# Matrix.net
KiCad netlist of a schematic drawn in EAGLE
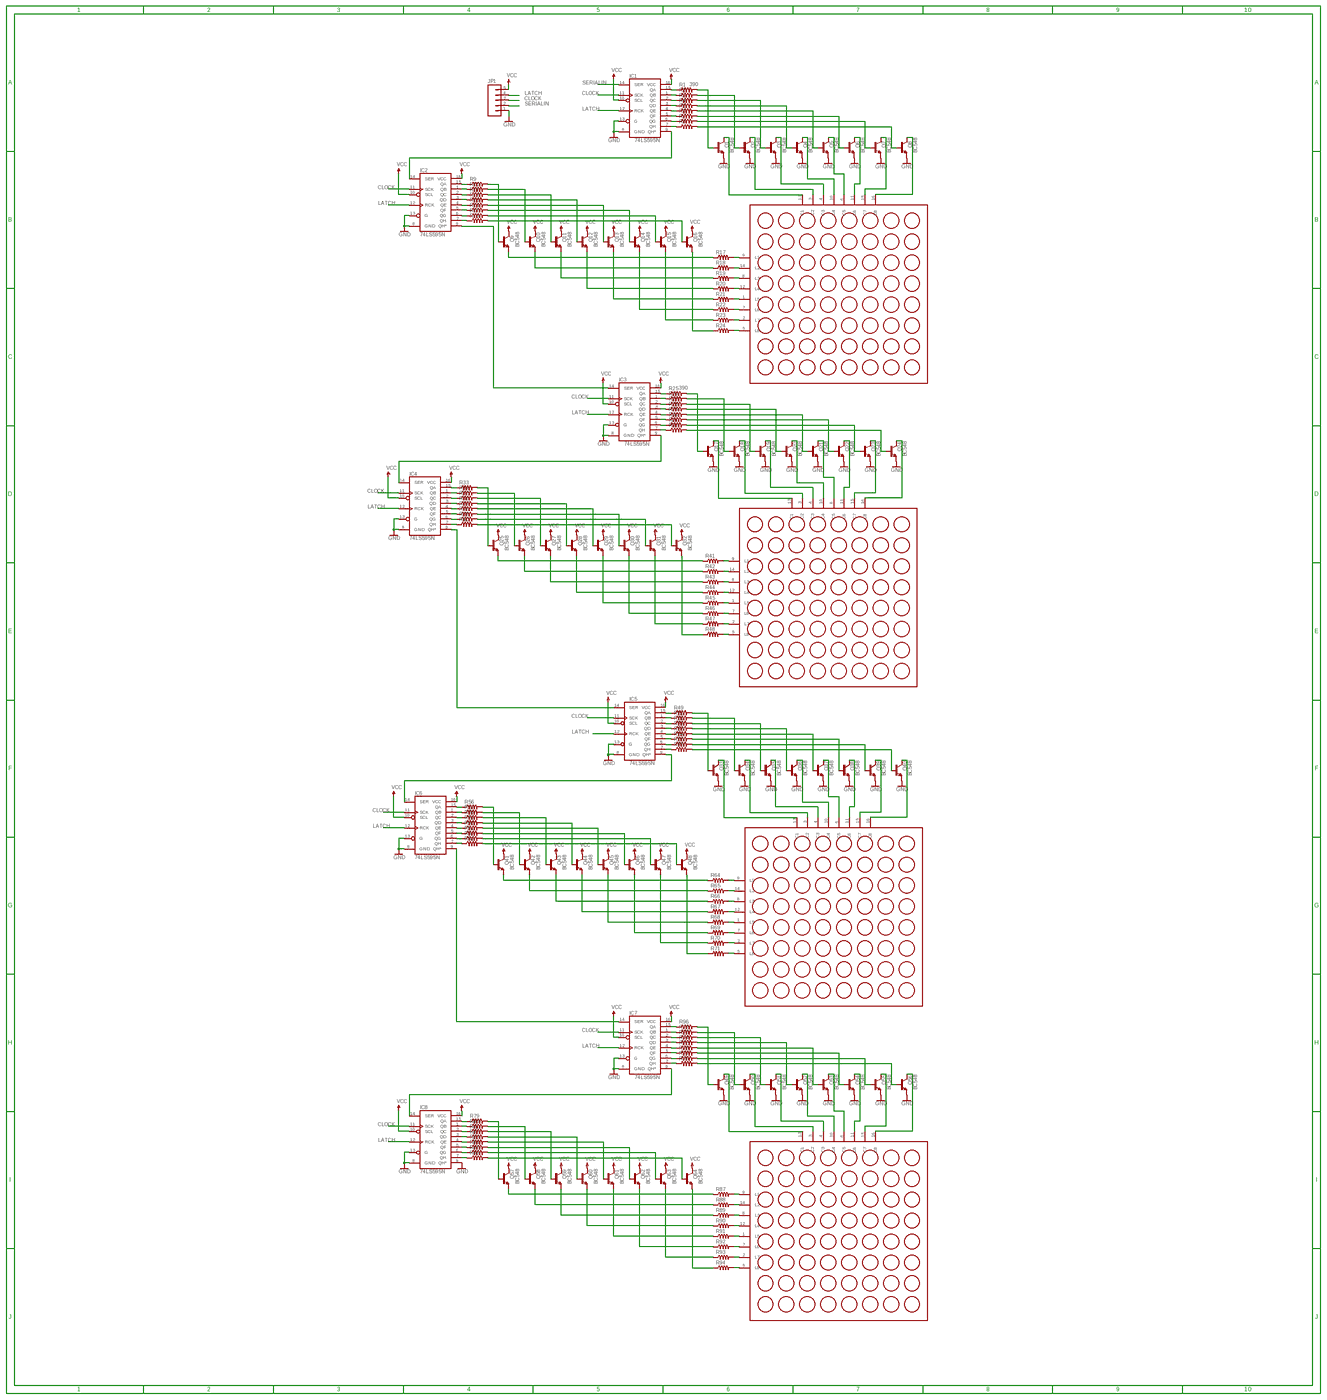
[diagram p0: schematic, sheet 1, overview]
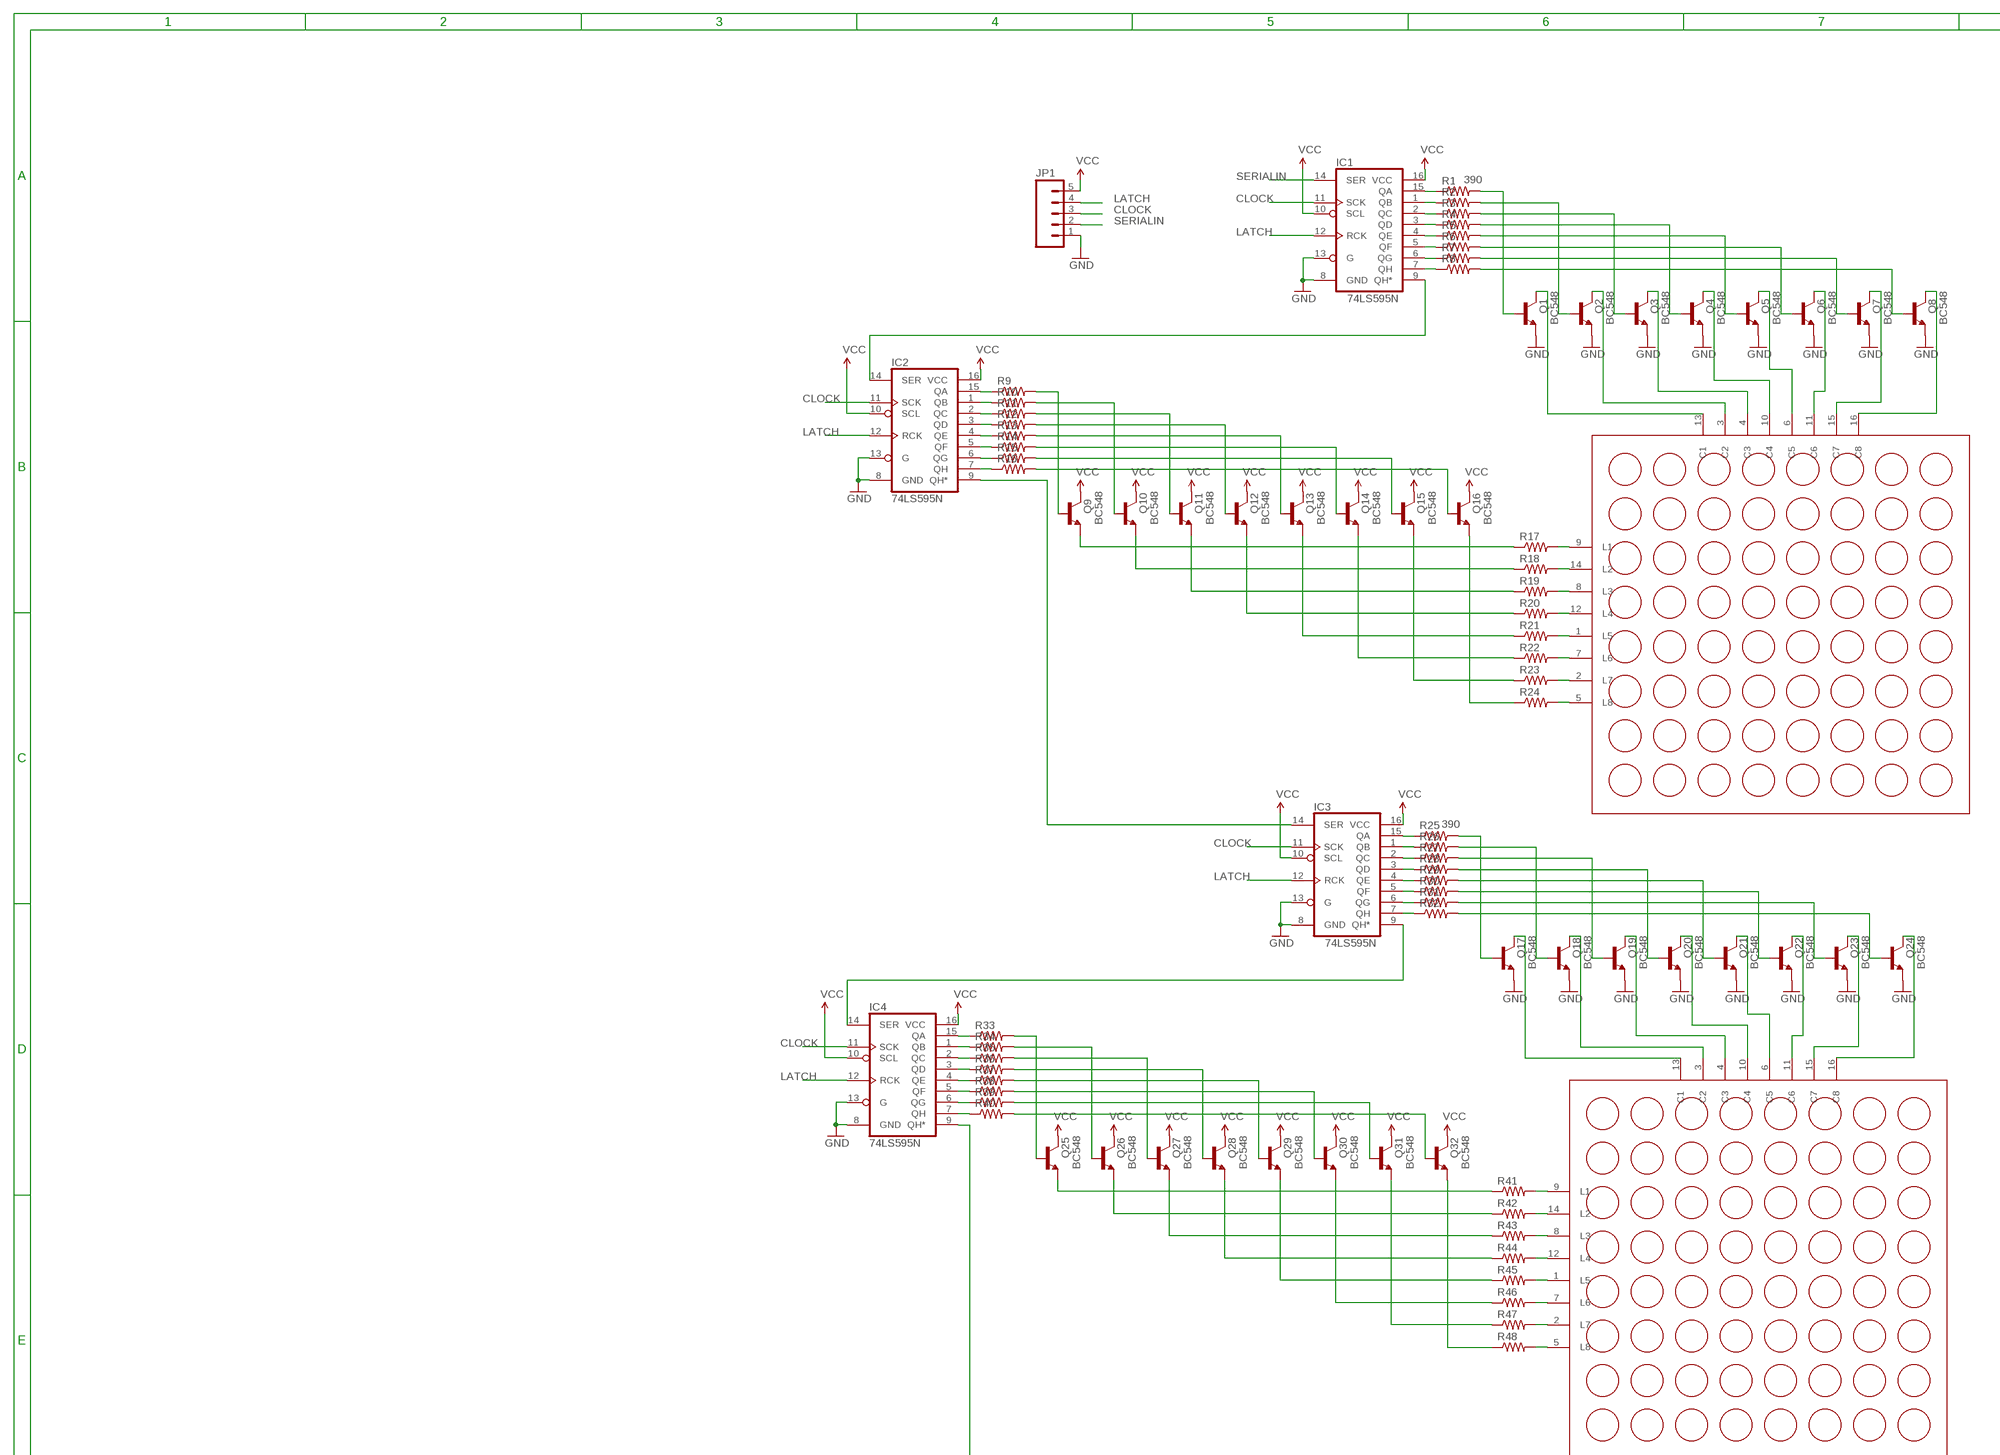
[diagram p1: schematic, sheet 1, part 1 of 4]
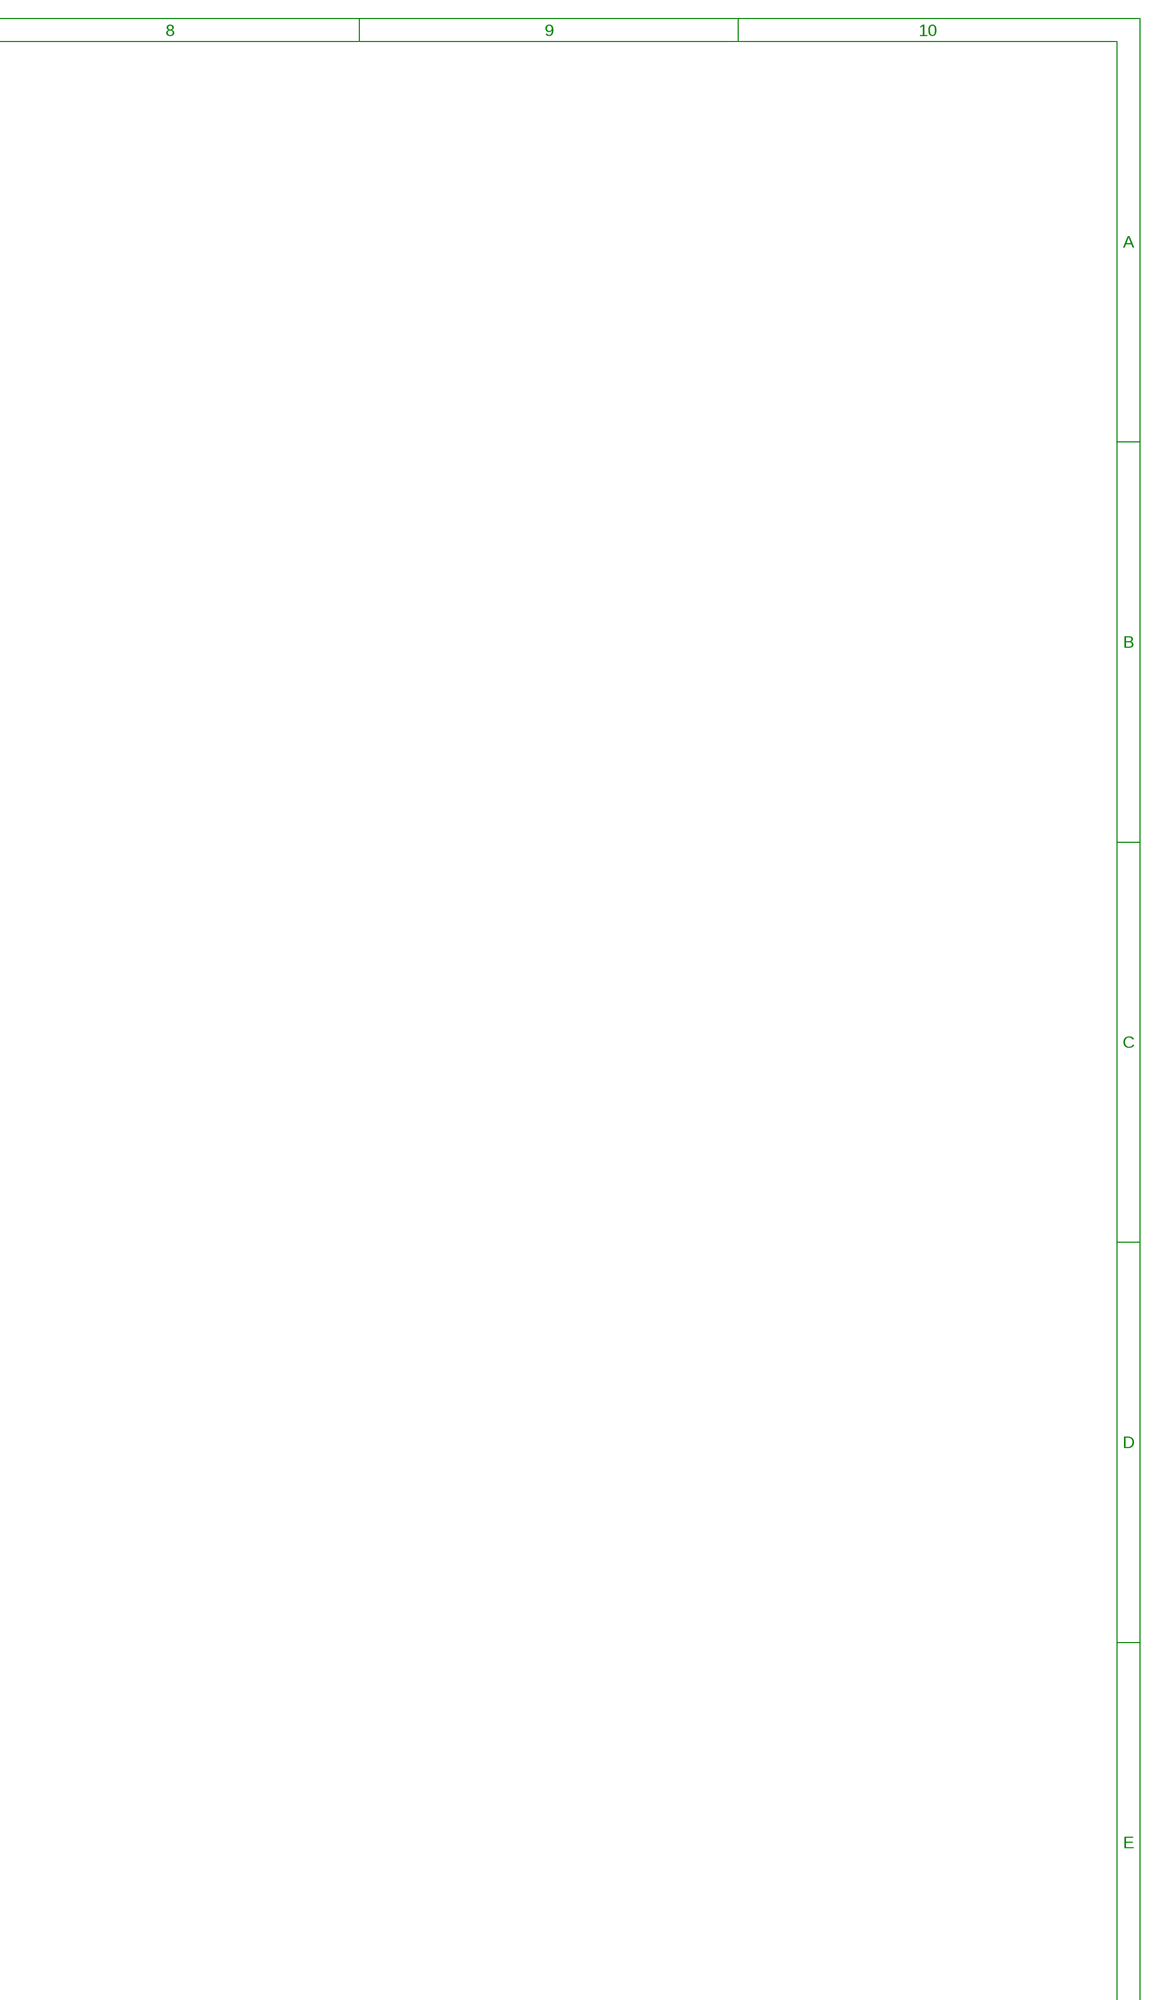
[diagram p2: schematic, sheet 1, part 2 of 4]
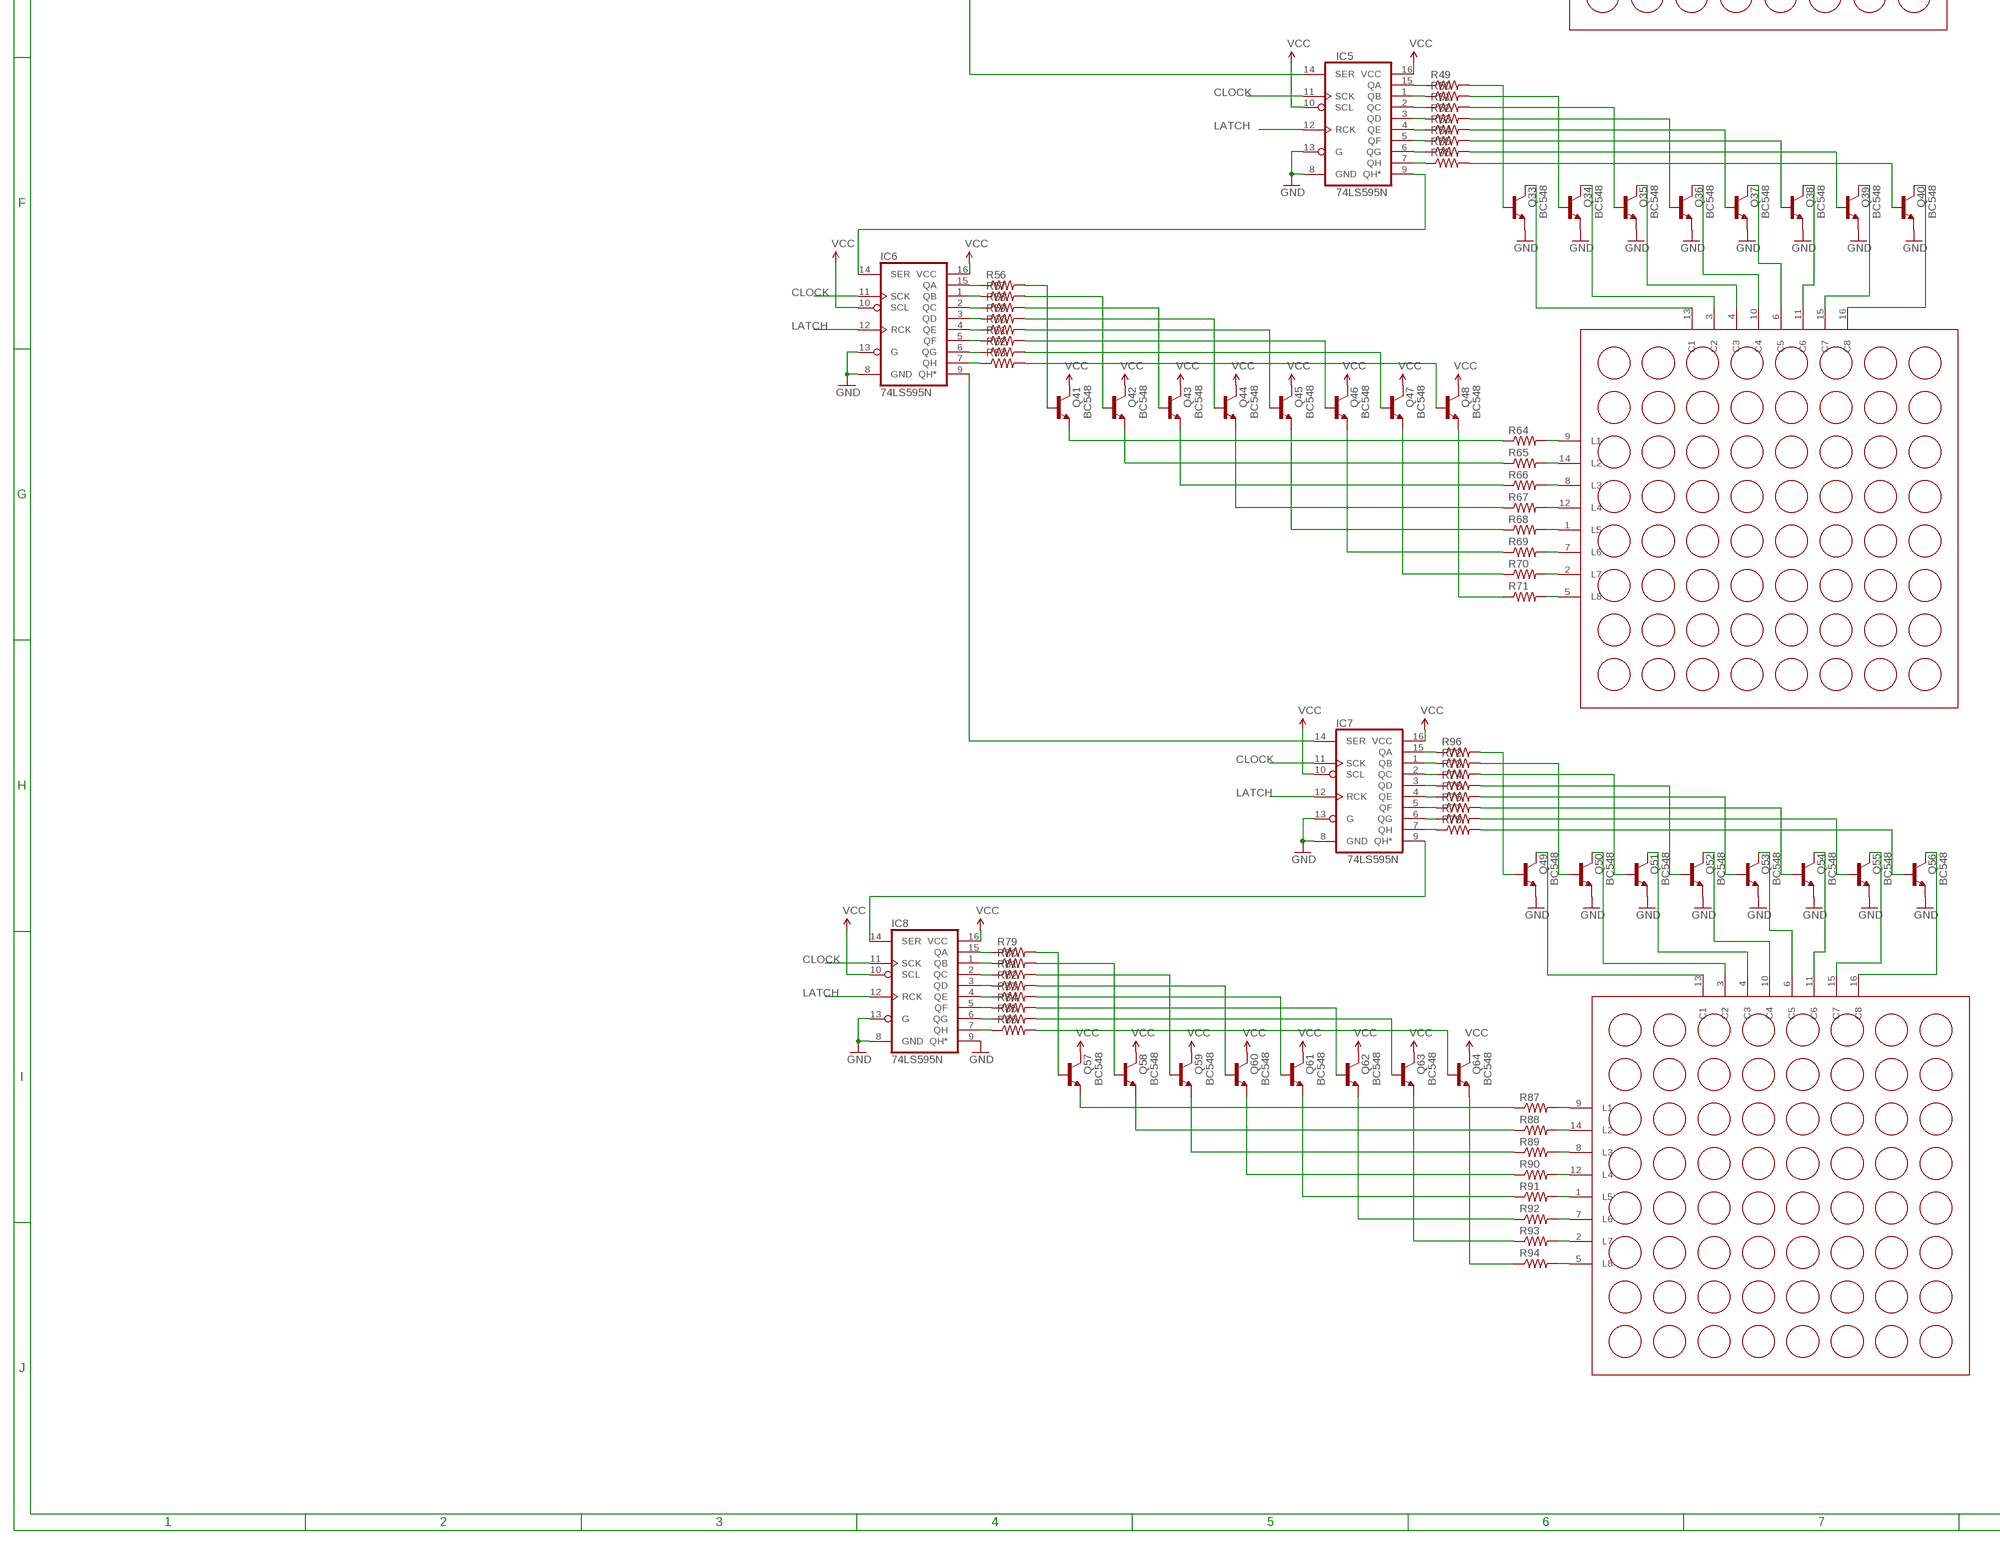
[diagram p3: schematic, sheet 1, part 3 of 4]
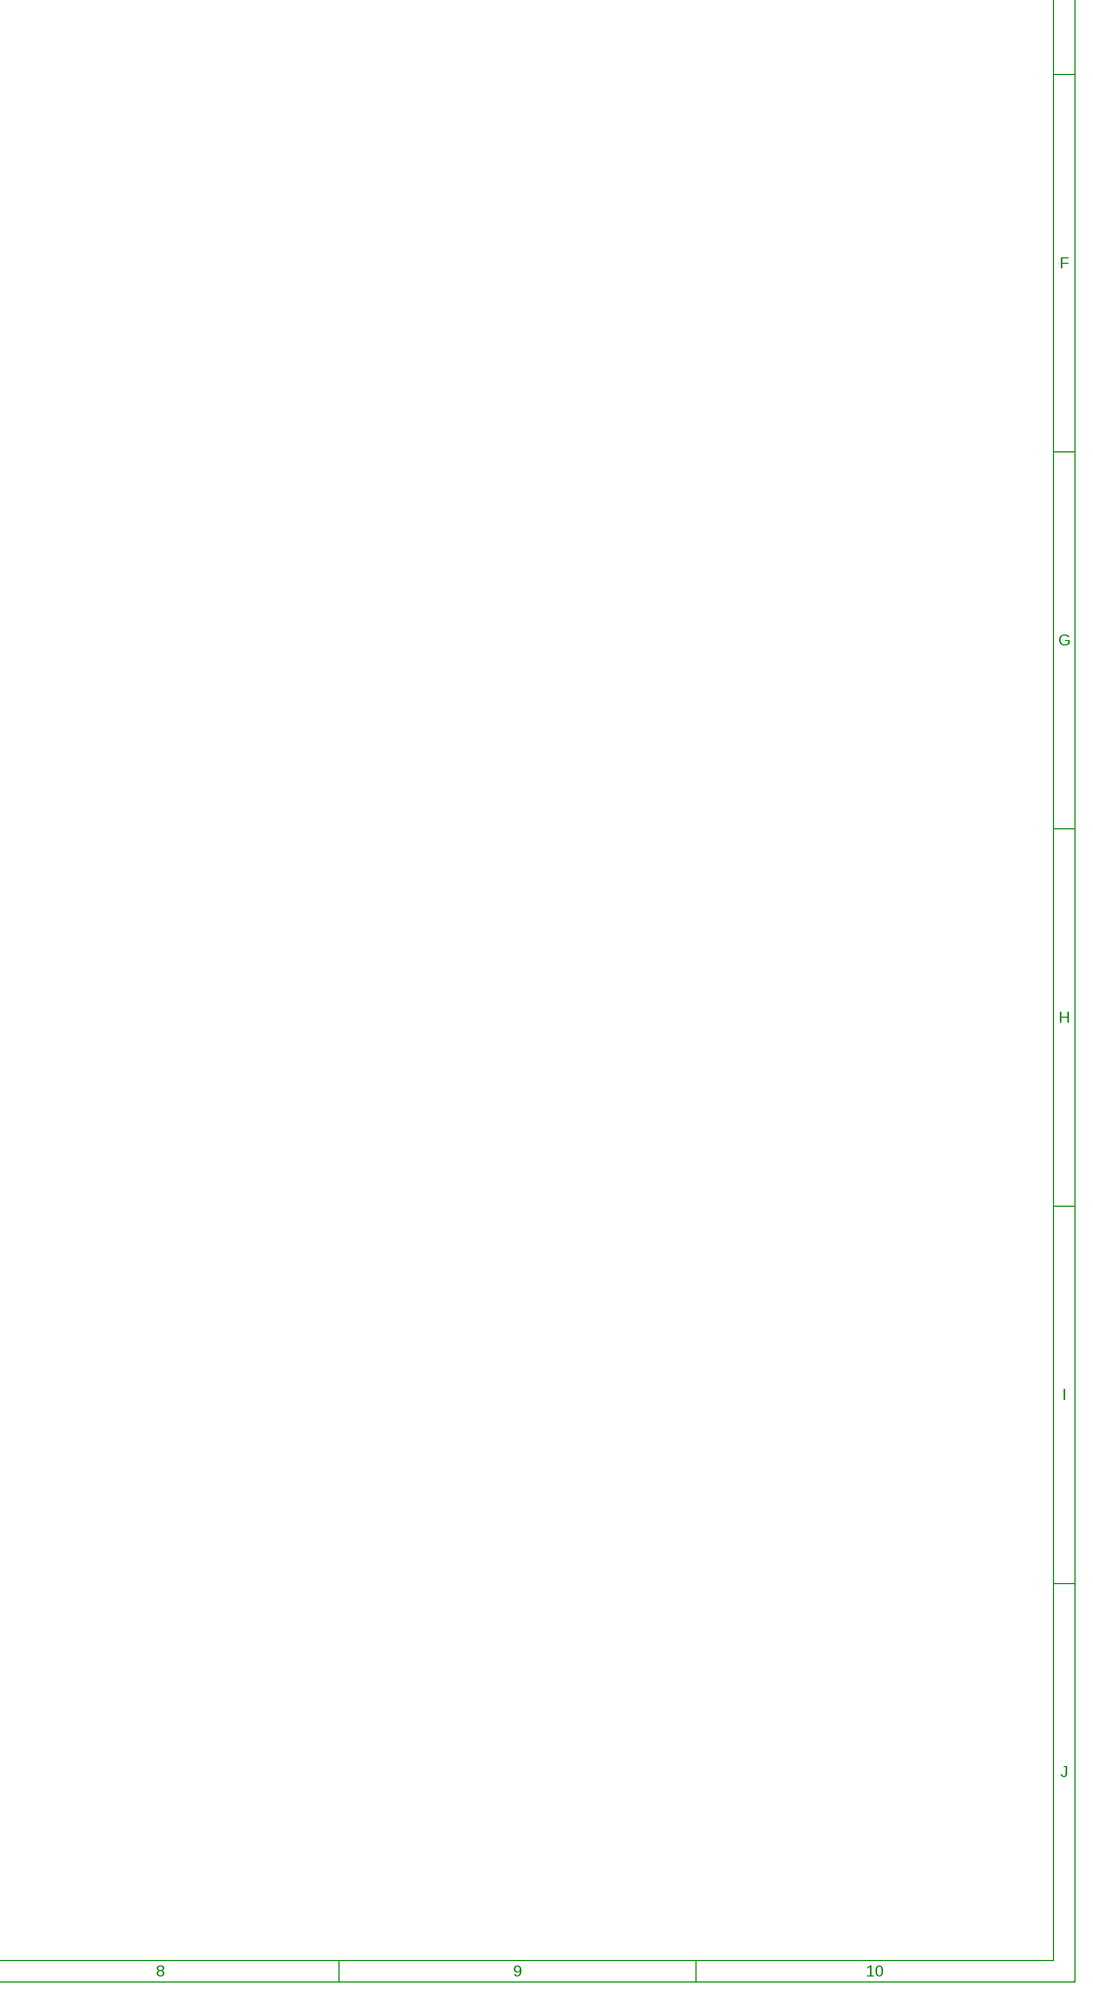
[diagram p4: schematic, sheet 1, part 4 of 4]
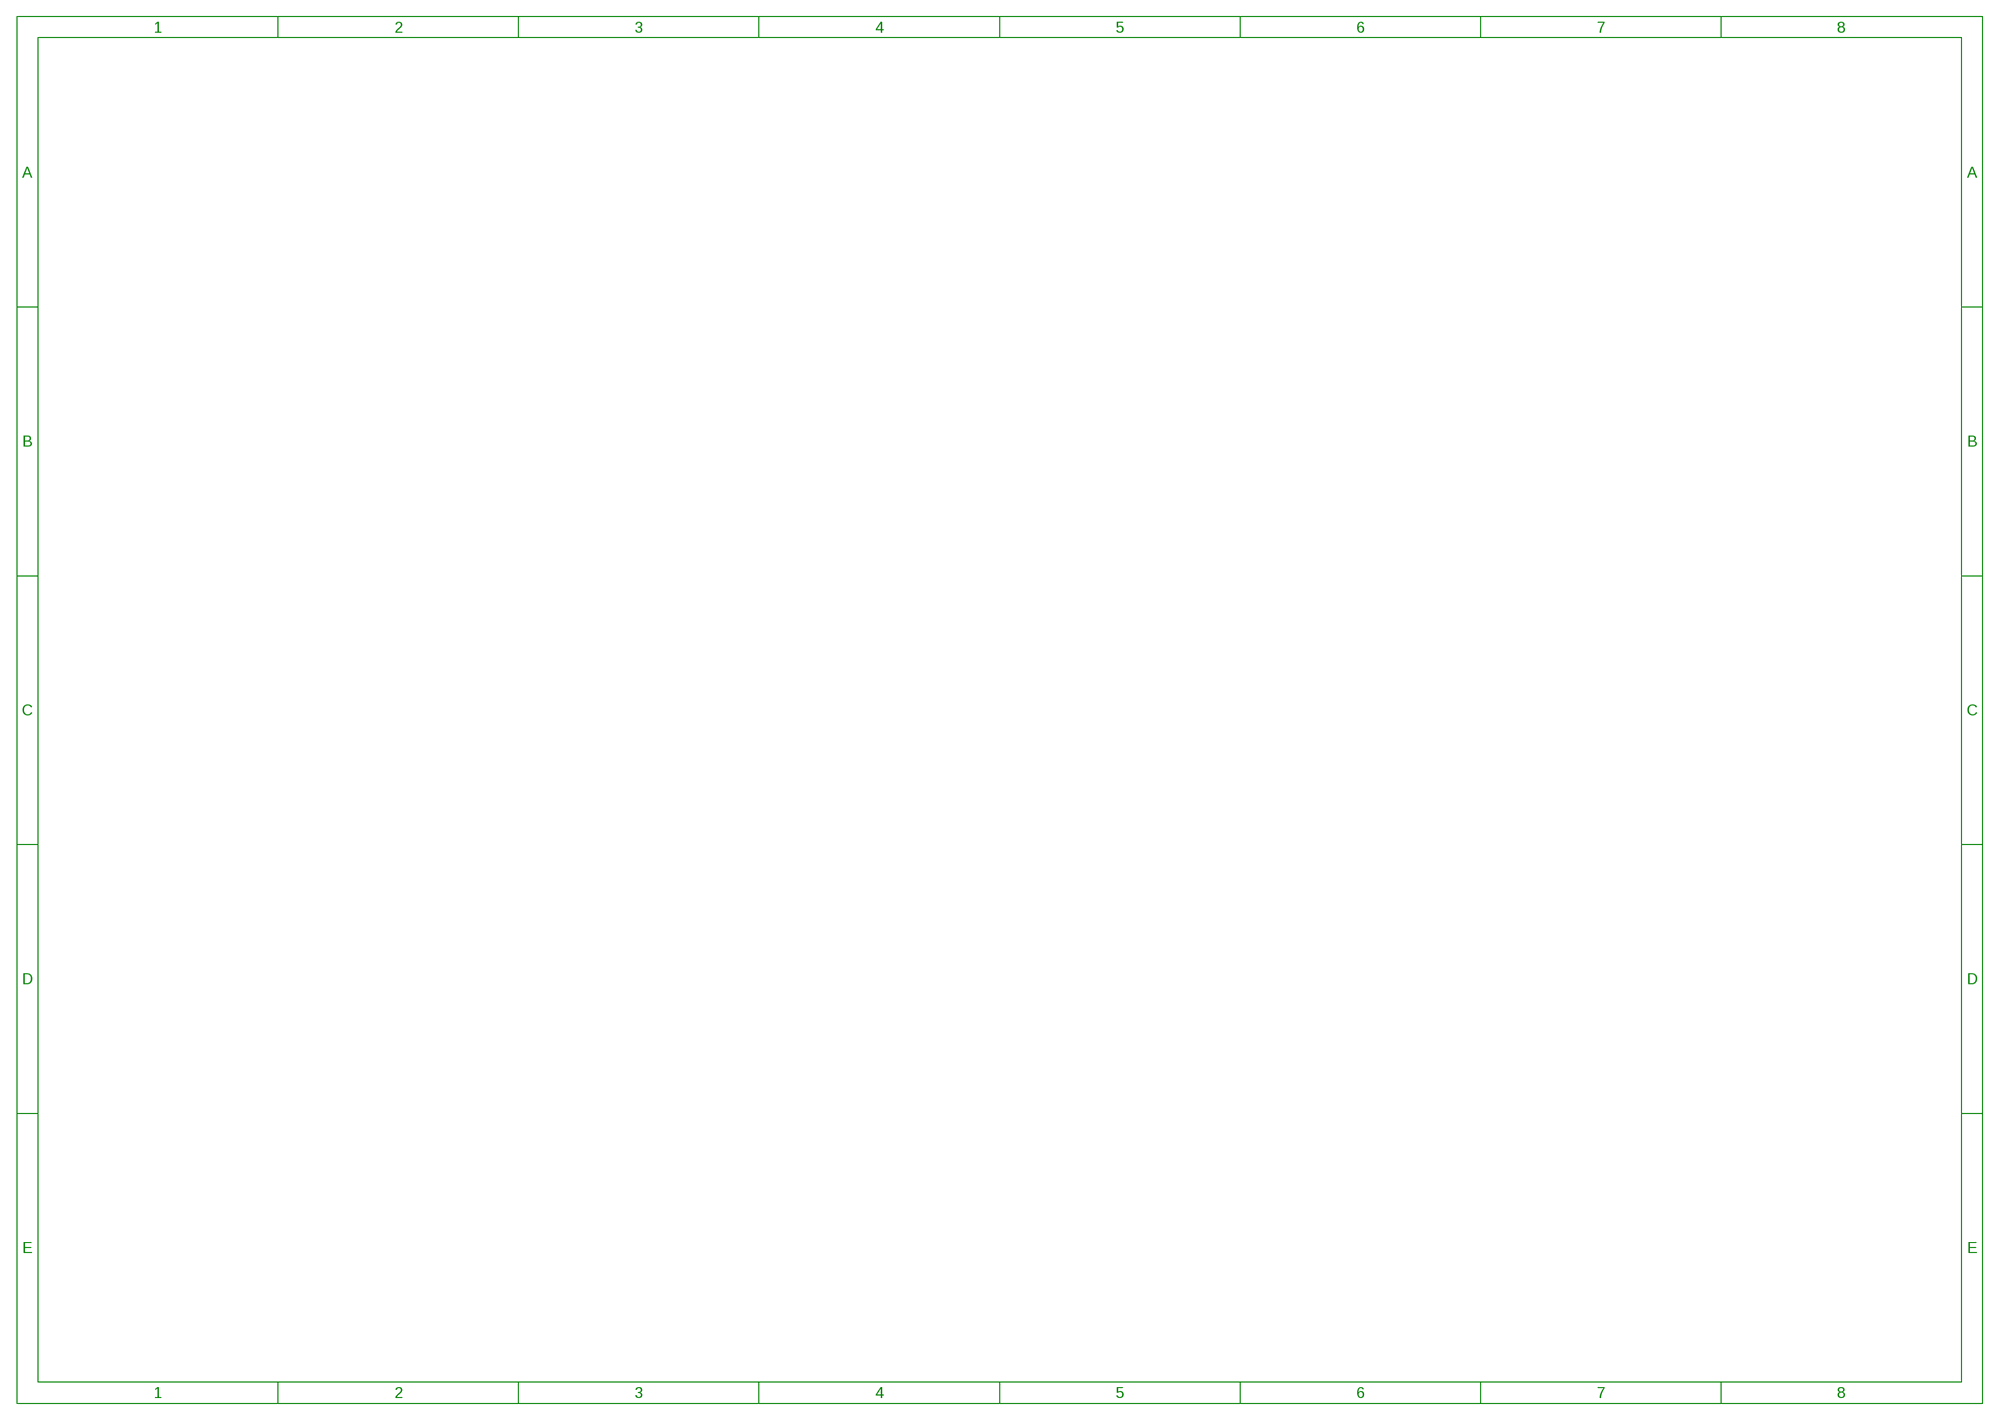
[diagram p5: schematic, sheet 2]

(export (version "E")
  (design (tool "Eeschema 10.0.6"))
  (components
    (comp (ref "IC1")
      (value "74LS595N")
      (footprint "eagle-import:DIL16")
      (libsource (lib "eagle-import") (part "74595NLS"))
    )
    (comp (ref "IC2")
      (value "74LS595N")
      (footprint "eagle-import:DIL16")
      (libsource (lib "eagle-import") (part "74595NLS"))
    )
    (comp (ref "IC3")
      (value "74LS595N")
      (footprint "eagle-import:DIL16")
      (libsource (lib "eagle-import") (part "74595NLS"))
    )
    (comp (ref "IC4")
      (value "74LS595N")
      (footprint "eagle-import:DIL16")
      (libsource (lib "eagle-import") (part "74595NLS"))
    )
    (comp (ref "IC5")
      (value "74LS595N")
      (footprint "eagle-import:DIL16")
      (libsource (lib "eagle-import") (part "74595NLS"))
    )
    (comp (ref "IC6")
      (value "74LS595N")
      (footprint "eagle-import:DIL16")
      (libsource (lib "eagle-import") (part "74595NLS"))
    )
    (comp (ref "IC7")
      (value "74LS595N")
      (footprint "eagle-import:DIL16")
      (libsource (lib "eagle-import") (part "74595NLS"))
    )
    (comp (ref "IC8")
      (value "74LS595N")
      (footprint "eagle-import:DIL16")
      (libsource (lib "eagle-import") (part "74595NLS"))
    )
    (comp (ref "JP1")
      (value "M05PTH_LONGPADS")
      (footprint "eagle-import:1X05_LONGPADS")
      (libsource (lib "eagle-import") (part "M05PTH_LONGPADS"))
    )
    (comp (ref "Q1")
      (value "BC548")
      (footprint "eagle-import:TO92-EBC")
      (libsource (lib "eagle-import") (part "BC548"))
    )
    (comp (ref "Q2")
      (value "BC548")
      (footprint "eagle-import:TO92-EBC")
      (libsource (lib "eagle-import") (part "BC548"))
    )
    (comp (ref "Q3")
      (value "BC548")
      (footprint "eagle-import:TO92-EBC")
      (libsource (lib "eagle-import") (part "BC548"))
    )
    (comp (ref "Q4")
      (value "BC548")
      (footprint "eagle-import:TO92-EBC")
      (libsource (lib "eagle-import") (part "BC548"))
    )
    (comp (ref "Q5")
      (value "BC548")
      (footprint "eagle-import:TO92-EBC")
      (libsource (lib "eagle-import") (part "BC548"))
    )
    (comp (ref "Q6")
      (value "BC548")
      (footprint "eagle-import:TO92-EBC")
      (libsource (lib "eagle-import") (part "BC548"))
    )
    (comp (ref "Q7")
      (value "BC548")
      (footprint "eagle-import:TO92-EBC")
      (libsource (lib "eagle-import") (part "BC548"))
    )
    (comp (ref "Q8")
      (value "BC548")
      (footprint "eagle-import:TO92-EBC")
      (libsource (lib "eagle-import") (part "BC548"))
    )
    (comp (ref "Q9")
      (value "BC548")
      (footprint "eagle-import:TO92-EBC")
      (libsource (lib "eagle-import") (part "BC548"))
    )
    (comp (ref "Q10")
      (value "BC548")
      (footprint "eagle-import:TO92-EBC")
      (libsource (lib "eagle-import") (part "BC548"))
    )
    (comp (ref "Q11")
      (value "BC548")
      (footprint "eagle-import:TO92-EBC")
      (libsource (lib "eagle-import") (part "BC548"))
    )
    (comp (ref "Q12")
      (value "BC548")
      (footprint "eagle-import:TO92-EBC")
      (libsource (lib "eagle-import") (part "BC548"))
    )
    (comp (ref "Q13")
      (value "BC548")
      (footprint "eagle-import:TO92-EBC")
      (libsource (lib "eagle-import") (part "BC548"))
    )
    (comp (ref "Q14")
      (value "BC548")
      (footprint "eagle-import:TO92-EBC")
      (libsource (lib "eagle-import") (part "BC548"))
    )
    (comp (ref "Q15")
      (value "BC548")
      (footprint "eagle-import:TO92-EBC")
      (libsource (lib "eagle-import") (part "BC548"))
    )
    (comp (ref "Q16")
      (value "BC548")
      (footprint "eagle-import:TO92-EBC")
      (libsource (lib "eagle-import") (part "BC548"))
    )
    (comp (ref "Q17")
      (value "BC548")
      (footprint "eagle-import:TO92-EBC")
      (libsource (lib "eagle-import") (part "BC548"))
    )
    (comp (ref "Q18")
      (value "BC548")
      (footprint "eagle-import:TO92-EBC")
      (libsource (lib "eagle-import") (part "BC548"))
    )
    (comp (ref "Q19")
      (value "BC548")
      (footprint "eagle-import:TO92-EBC")
      (libsource (lib "eagle-import") (part "BC548"))
    )
    (comp (ref "Q20")
      (value "BC548")
      (footprint "eagle-import:TO92-EBC")
      (libsource (lib "eagle-import") (part "BC548"))
    )
    (comp (ref "Q21")
      (value "BC548")
      (footprint "eagle-import:TO92-EBC")
      (libsource (lib "eagle-import") (part "BC548"))
    )
    (comp (ref "Q22")
      (value "BC548")
      (footprint "eagle-import:TO92-EBC")
      (libsource (lib "eagle-import") (part "BC548"))
    )
    (comp (ref "Q23")
      (value "BC548")
      (footprint "eagle-import:TO92-EBC")
      (libsource (lib "eagle-import") (part "BC548"))
    )
    (comp (ref "Q24")
      (value "BC548")
      (footprint "eagle-import:TO92-EBC")
      (libsource (lib "eagle-import") (part "BC548"))
    )
    (comp (ref "Q25")
      (value "BC548")
      (footprint "eagle-import:TO92-EBC")
      (libsource (lib "eagle-import") (part "BC548"))
    )
    (comp (ref "Q26")
      (value "BC548")
      (footprint "eagle-import:TO92-EBC")
      (libsource (lib "eagle-import") (part "BC548"))
    )
    (comp (ref "Q27")
      (value "BC548")
      (footprint "eagle-import:TO92-EBC")
      (libsource (lib "eagle-import") (part "BC548"))
    )
    (comp (ref "Q28")
      (value "BC548")
      (footprint "eagle-import:TO92-EBC")
      (libsource (lib "eagle-import") (part "BC548"))
    )
    (comp (ref "Q29")
      (value "BC548")
      (footprint "eagle-import:TO92-EBC")
      (libsource (lib "eagle-import") (part "BC548"))
    )
    (comp (ref "Q30")
      (value "BC548")
      (footprint "eagle-import:TO92-EBC")
      (libsource (lib "eagle-import") (part "BC548"))
    )
    (comp (ref "Q31")
      (value "BC548")
      (footprint "eagle-import:TO92-EBC")
      (libsource (lib "eagle-import") (part "BC548"))
    )
    (comp (ref "Q32")
      (value "BC548")
      (footprint "eagle-import:TO92-EBC")
      (libsource (lib "eagle-import") (part "BC548"))
    )
    (comp (ref "Q33")
      (value "BC548")
      (footprint "eagle-import:TO92-EBC")
      (libsource (lib "eagle-import") (part "BC548"))
    )
    (comp (ref "Q34")
      (value "BC548")
      (footprint "eagle-import:TO92-EBC")
      (libsource (lib "eagle-import") (part "BC548"))
    )
    (comp (ref "Q35")
      (value "BC548")
      (footprint "eagle-import:TO92-EBC")
      (libsource (lib "eagle-import") (part "BC548"))
    )
    (comp (ref "Q36")
      (value "BC548")
      (footprint "eagle-import:TO92-EBC")
      (libsource (lib "eagle-import") (part "BC548"))
    )
    (comp (ref "Q37")
      (value "BC548")
      (footprint "eagle-import:TO92-EBC")
      (libsource (lib "eagle-import") (part "BC548"))
    )
    (comp (ref "Q38")
      (value "BC548")
      (footprint "eagle-import:TO92-EBC")
      (libsource (lib "eagle-import") (part "BC548"))
    )
    (comp (ref "Q39")
      (value "BC548")
      (footprint "eagle-import:TO92-EBC")
      (libsource (lib "eagle-import") (part "BC548"))
    )
    (comp (ref "Q40")
      (value "BC548")
      (footprint "eagle-import:TO92-EBC")
      (libsource (lib "eagle-import") (part "BC548"))
    )
    (comp (ref "Q41")
      (value "BC548")
      (footprint "eagle-import:TO92-EBC")
      (libsource (lib "eagle-import") (part "BC548"))
    )
    (comp (ref "Q42")
      (value "BC548")
      (footprint "eagle-import:TO92-EBC")
      (libsource (lib "eagle-import") (part "BC548"))
    )
    (comp (ref "Q43")
      (value "BC548")
      (footprint "eagle-import:TO92-EBC")
      (libsource (lib "eagle-import") (part "BC548"))
    )
    (comp (ref "Q44")
      (value "BC548")
      (footprint "eagle-import:TO92-EBC")
      (libsource (lib "eagle-import") (part "BC548"))
    )
    (comp (ref "Q45")
      (value "BC548")
      (footprint "eagle-import:TO92-EBC")
      (libsource (lib "eagle-import") (part "BC548"))
    )
    (comp (ref "Q46")
      (value "BC548")
      (footprint "eagle-import:TO92-EBC")
      (libsource (lib "eagle-import") (part "BC548"))
    )
    (comp (ref "Q47")
      (value "BC548")
      (footprint "eagle-import:TO92-EBC")
      (libsource (lib "eagle-import") (part "BC548"))
    )
    (comp (ref "Q48")
      (value "BC548")
      (footprint "eagle-import:TO92-EBC")
      (libsource (lib "eagle-import") (part "BC548"))
    )
    (comp (ref "Q49")
      (value "BC548")
      (footprint "eagle-import:TO92-EBC")
      (libsource (lib "eagle-import") (part "BC548"))
    )
    (comp (ref "Q50")
      (value "BC548")
      (footprint "eagle-import:TO92-EBC")
      (libsource (lib "eagle-import") (part "BC548"))
    )
    (comp (ref "Q51")
      (value "BC548")
      (footprint "eagle-import:TO92-EBC")
      (libsource (lib "eagle-import") (part "BC548"))
    )
    (comp (ref "Q52")
      (value "BC548")
      (footprint "eagle-import:TO92-EBC")
      (libsource (lib "eagle-import") (part "BC548"))
    )
    (comp (ref "Q53")
      (value "BC548")
      (footprint "eagle-import:TO92-EBC")
      (libsource (lib "eagle-import") (part "BC548"))
    )
    (comp (ref "Q54")
      (value "BC548")
      (footprint "eagle-import:TO92-EBC")
      (libsource (lib "eagle-import") (part "BC548"))
    )
    (comp (ref "Q55")
      (value "BC548")
      (footprint "eagle-import:TO92-EBC")
      (libsource (lib "eagle-import") (part "BC548"))
    )
    (comp (ref "Q56")
      (value "BC548")
      (footprint "eagle-import:TO92-EBC")
      (libsource (lib "eagle-import") (part "BC548"))
    )
    (comp (ref "Q57")
      (value "BC548")
      (footprint "eagle-import:TO92-EBC")
      (libsource (lib "eagle-import") (part "BC548"))
    )
    (comp (ref "Q58")
      (value "BC548")
      (footprint "eagle-import:TO92-EBC")
      (libsource (lib "eagle-import") (part "BC548"))
    )
    (comp (ref "Q59")
      (value "BC548")
      (footprint "eagle-import:TO92-EBC")
      (libsource (lib "eagle-import") (part "BC548"))
    )
    (comp (ref "Q60")
      (value "BC548")
      (footprint "eagle-import:TO92-EBC")
      (libsource (lib "eagle-import") (part "BC548"))
    )
    (comp (ref "Q61")
      (value "BC548")
      (footprint "eagle-import:TO92-EBC")
      (libsource (lib "eagle-import") (part "BC548"))
    )
    (comp (ref "Q62")
      (value "BC548")
      (footprint "eagle-import:TO92-EBC")
      (libsource (lib "eagle-import") (part "BC548"))
    )
    (comp (ref "Q63")
      (value "BC548")
      (footprint "eagle-import:TO92-EBC")
      (libsource (lib "eagle-import") (part "BC548"))
    )
    (comp (ref "Q64")
      (value "BC548")
      (footprint "eagle-import:TO92-EBC")
      (libsource (lib "eagle-import") (part "BC548"))
    )
    (comp (ref "R1")
      (value "390")
      (footprint "eagle-import:AXIAL-0.4")
      (libsource (lib "eagle-import") (part "RESISTORPTH-1/4W"))
    )
    (comp (ref "R2")
      (value "390")
      (footprint "eagle-import:AXIAL-0.4")
      (libsource (lib "eagle-import") (part "RESISTORPTH-1/4W"))
    )
    (comp (ref "R3")
      (value "390")
      (footprint "eagle-import:AXIAL-0.4")
      (libsource (lib "eagle-import") (part "RESISTORPTH-1/4W"))
    )
    (comp (ref "R4")
      (value "390")
      (footprint "eagle-import:AXIAL-0.4")
      (libsource (lib "eagle-import") (part "RESISTORPTH-1/4W"))
    )
    (comp (ref "R5")
      (value "390")
      (footprint "eagle-import:AXIAL-0.4")
      (libsource (lib "eagle-import") (part "RESISTORPTH-1/4W"))
    )
    (comp (ref "R6")
      (value "390")
      (footprint "eagle-import:AXIAL-0.4")
      (libsource (lib "eagle-import") (part "RESISTORPTH-1/4W"))
    )
    (comp (ref "R7")
      (value "390")
      (footprint "eagle-import:AXIAL-0.4")
      (libsource (lib "eagle-import") (part "RESISTORPTH-1/4W"))
    )
    (comp (ref "R8")
      (value "390")
      (footprint "eagle-import:AXIAL-0.4")
      (libsource (lib "eagle-import") (part "RESISTORPTH-1/4W"))
    )
    (comp (ref "R9")
      (value "390")
      (footprint "eagle-import:AXIAL-0.4")
      (libsource (lib "eagle-import") (part "RESISTORPTH-1/4W"))
    )
    (comp (ref "R10")
      (value "390")
      (footprint "eagle-import:AXIAL-0.4")
      (libsource (lib "eagle-import") (part "RESISTORPTH-1/4W"))
    )
    (comp (ref "R11")
      (value "390")
      (footprint "eagle-import:AXIAL-0.4")
      (libsource (lib "eagle-import") (part "RESISTORPTH-1/4W"))
    )
    (comp (ref "R12")
      (value "390")
      (footprint "eagle-import:AXIAL-0.4")
      (libsource (lib "eagle-import") (part "RESISTORPTH-1/4W"))
    )
    (comp (ref "R13")
      (value "390")
      (footprint "eagle-import:AXIAL-0.4")
      (libsource (lib "eagle-import") (part "RESISTORPTH-1/4W"))
    )
    (comp (ref "R14")
      (value "390")
      (footprint "eagle-import:AXIAL-0.4")
      (libsource (lib "eagle-import") (part "RESISTORPTH-1/4W"))
    )
    (comp (ref "R15")
      (value "390")
      (footprint "eagle-import:AXIAL-0.4")
      (libsource (lib "eagle-import") (part "RESISTORPTH-1/4W"))
    )
    (comp (ref "R16")
      (value "390")
      (footprint "eagle-import:AXIAL-0.4")
      (libsource (lib "eagle-import") (part "RESISTORPTH-1/4W"))
    )
    (comp (ref "R17")
      (value "390")
      (footprint "eagle-import:AXIAL-0.4")
      (libsource (lib "eagle-import") (part "RESISTORPTH-1/4W"))
    )
    (comp (ref "R18")
      (value "390")
      (footprint "eagle-import:AXIAL-0.4")
      (libsource (lib "eagle-import") (part "RESISTORPTH-1/4W"))
    )
    (comp (ref "R19")
      (value "390")
      (footprint "eagle-import:AXIAL-0.4")
      (libsource (lib "eagle-import") (part "RESISTORPTH-1/4W"))
    )
    (comp (ref "R20")
      (value "390")
      (footprint "eagle-import:AXIAL-0.4")
      (libsource (lib "eagle-import") (part "RESISTORPTH-1/4W"))
    )
    (comp (ref "R21")
      (value "390")
      (footprint "eagle-import:AXIAL-0.4")
      (libsource (lib "eagle-import") (part "RESISTORPTH-1/4W"))
    )
    (comp (ref "R22")
      (value "390")
      (footprint "eagle-import:AXIAL-0.4")
      (libsource (lib "eagle-import") (part "RESISTORPTH-1/4W"))
    )
    (comp (ref "R23")
      (value "390")
      (footprint "eagle-import:AXIAL-0.4")
      (libsource (lib "eagle-import") (part "RESISTORPTH-1/4W"))
    )
    (comp (ref "R24")
      (value "390")
      (footprint "eagle-import:AXIAL-0.4")
      (libsource (lib "eagle-import") (part "RESISTORPTH-1/4W"))
    )
    (comp (ref "R25")
      (value "390")
      (footprint "eagle-import:AXIAL-0.4")
      (libsource (lib "eagle-import") (part "RESISTORPTH-1/4W"))
    )
    (comp (ref "R26")
      (value "390")
      (footprint "eagle-import:AXIAL-0.4")
      (libsource (lib "eagle-import") (part "RESISTORPTH-1/4W"))
    )
    (comp (ref "R27")
      (value "390")
      (footprint "eagle-import:AXIAL-0.4")
      (libsource (lib "eagle-import") (part "RESISTORPTH-1/4W"))
    )
    (comp (ref "R28")
      (value "390")
      (footprint "eagle-import:AXIAL-0.4")
      (libsource (lib "eagle-import") (part "RESISTORPTH-1/4W"))
    )
    (comp (ref "R29")
      (value "390")
      (footprint "eagle-import:AXIAL-0.4")
      (libsource (lib "eagle-import") (part "RESISTORPTH-1/4W"))
    )
    (comp (ref "R30")
      (value "390")
      (footprint "eagle-import:AXIAL-0.4")
      (libsource (lib "eagle-import") (part "RESISTORPTH-1/4W"))
    )
    (comp (ref "R31")
      (value "390")
      (footprint "eagle-import:AXIAL-0.4")
      (libsource (lib "eagle-import") (part "RESISTORPTH-1/4W"))
    )
    (comp (ref "R32")
      (value "390")
      (footprint "eagle-import:AXIAL-0.4")
      (libsource (lib "eagle-import") (part "RESISTORPTH-1/4W"))
    )
    (comp (ref "R33")
      (value "390")
      (footprint "eagle-import:AXIAL-0.4")
      (libsource (lib "eagle-import") (part "RESISTORPTH-1/4W"))
    )
    (comp (ref "R34")
      (value "390")
      (footprint "eagle-import:AXIAL-0.4")
      (libsource (lib "eagle-import") (part "RESISTORPTH-1/4W"))
    )
    (comp (ref "R35")
      (value "390")
      (footprint "eagle-import:AXIAL-0.4")
      (libsource (lib "eagle-import") (part "RESISTORPTH-1/4W"))
    )
    (comp (ref "R36")
      (value "390")
      (footprint "eagle-import:AXIAL-0.4")
      (libsource (lib "eagle-import") (part "RESISTORPTH-1/4W"))
    )
    (comp (ref "R37")
      (value "390")
      (footprint "eagle-import:AXIAL-0.4")
      (libsource (lib "eagle-import") (part "RESISTORPTH-1/4W"))
    )
    (comp (ref "R38")
      (value "390")
      (footprint "eagle-import:AXIAL-0.4")
      (libsource (lib "eagle-import") (part "RESISTORPTH-1/4W"))
    )
    (comp (ref "R39")
      (value "390")
      (footprint "eagle-import:AXIAL-0.4")
      (libsource (lib "eagle-import") (part "RESISTORPTH-1/4W"))
    )
    (comp (ref "R40")
      (value "390")
      (footprint "eagle-import:AXIAL-0.4")
      (libsource (lib "eagle-import") (part "RESISTORPTH-1/4W"))
    )
    (comp (ref "R41")
      (value "390")
      (footprint "eagle-import:AXIAL-0.4")
      (libsource (lib "eagle-import") (part "RESISTORPTH-1/4W"))
    )
    (comp (ref "R42")
      (value "390")
      (footprint "eagle-import:AXIAL-0.4")
      (libsource (lib "eagle-import") (part "RESISTORPTH-1/4W"))
    )
    (comp (ref "R43")
      (value "390")
      (footprint "eagle-import:AXIAL-0.4")
      (libsource (lib "eagle-import") (part "RESISTORPTH-1/4W"))
    )
    (comp (ref "R44")
      (value "390")
      (footprint "eagle-import:AXIAL-0.4")
      (libsource (lib "eagle-import") (part "RESISTORPTH-1/4W"))
    )
    (comp (ref "R45")
      (value "390")
      (footprint "eagle-import:AXIAL-0.4")
      (libsource (lib "eagle-import") (part "RESISTORPTH-1/4W"))
    )
    (comp (ref "R46")
      (value "390")
      (footprint "eagle-import:AXIAL-0.4")
      (libsource (lib "eagle-import") (part "RESISTORPTH-1/4W"))
    )
    (comp (ref "R47")
      (value "390")
      (footprint "eagle-import:AXIAL-0.4")
      (libsource (lib "eagle-import") (part "RESISTORPTH-1/4W"))
    )
    (comp (ref "R48")
      (value "390")
      (footprint "eagle-import:AXIAL-0.4")
      (libsource (lib "eagle-import") (part "RESISTORPTH-1/4W"))
    )
    (comp (ref "R49")
      (value "390")
      (footprint "eagle-import:AXIAL-0.4")
      (libsource (lib "eagle-import") (part "RESISTORPTH-1/4W"))
    )
    (comp (ref "R50")
      (value "390")
      (footprint "eagle-import:AXIAL-0.4")
      (libsource (lib "eagle-import") (part "RESISTORPTH-1/4W"))
    )
    (comp (ref "R51")
      (value "390")
      (footprint "eagle-import:AXIAL-0.4")
      (libsource (lib "eagle-import") (part "RESISTORPTH-1/4W"))
    )
    (comp (ref "R52")
      (value "390")
      (footprint "eagle-import:AXIAL-0.4")
      (libsource (lib "eagle-import") (part "RESISTORPTH-1/4W"))
    )
    (comp (ref "R53")
      (value "390")
      (footprint "eagle-import:AXIAL-0.4")
      (libsource (lib "eagle-import") (part "RESISTORPTH-1/4W"))
    )
    (comp (ref "R54")
      (value "390")
      (footprint "eagle-import:AXIAL-0.4")
      (libsource (lib "eagle-import") (part "RESISTORPTH-1/4W"))
    )
    (comp (ref "R55")
      (value "390")
      (footprint "eagle-import:AXIAL-0.4")
      (libsource (lib "eagle-import") (part "RESISTORPTH-1/4W"))
    )
    (comp (ref "R56")
      (value "390")
      (footprint "eagle-import:AXIAL-0.4")
      (libsource (lib "eagle-import") (part "RESISTORPTH-1/4W"))
    )
    (comp (ref "R57")
      (value "390")
      (footprint "eagle-import:AXIAL-0.4")
      (libsource (lib "eagle-import") (part "RESISTORPTH-1/4W"))
    )
    (comp (ref "R58")
      (value "390")
      (footprint "eagle-import:AXIAL-0.4")
      (libsource (lib "eagle-import") (part "RESISTORPTH-1/4W"))
    )
    (comp (ref "R59")
      (value "390")
      (footprint "eagle-import:AXIAL-0.4")
      (libsource (lib "eagle-import") (part "RESISTORPTH-1/4W"))
    )
    (comp (ref "R60")
      (value "390")
      (footprint "eagle-import:AXIAL-0.4")
      (libsource (lib "eagle-import") (part "RESISTORPTH-1/4W"))
    )
    (comp (ref "R61")
      (value "390")
      (footprint "eagle-import:AXIAL-0.4")
      (libsource (lib "eagle-import") (part "RESISTORPTH-1/4W"))
    )
    (comp (ref "R62")
      (value "390")
      (footprint "eagle-import:AXIAL-0.4")
      (libsource (lib "eagle-import") (part "RESISTORPTH-1/4W"))
    )
    (comp (ref "R63")
      (value "390")
      (footprint "eagle-import:AXIAL-0.4")
      (libsource (lib "eagle-import") (part "RESISTORPTH-1/4W"))
    )
    (comp (ref "R64")
      (value "390")
      (footprint "eagle-import:AXIAL-0.4")
      (libsource (lib "eagle-import") (part "RESISTORPTH-1/4W"))
    )
    (comp (ref "R65")
      (value "390")
      (footprint "eagle-import:AXIAL-0.4")
      (libsource (lib "eagle-import") (part "RESISTORPTH-1/4W"))
    )
    (comp (ref "R66")
      (value "390")
      (footprint "eagle-import:AXIAL-0.4")
      (libsource (lib "eagle-import") (part "RESISTORPTH-1/4W"))
    )
    (comp (ref "R67")
      (value "390")
      (footprint "eagle-import:AXIAL-0.4")
      (libsource (lib "eagle-import") (part "RESISTORPTH-1/4W"))
    )
    (comp (ref "R68")
      (value "390")
      (footprint "eagle-import:AXIAL-0.4")
      (libsource (lib "eagle-import") (part "RESISTORPTH-1/4W"))
    )
    (comp (ref "R69")
      (value "390")
      (footprint "eagle-import:AXIAL-0.4")
      (libsource (lib "eagle-import") (part "RESISTORPTH-1/4W"))
    )
    (comp (ref "R70")
      (value "390")
      (footprint "eagle-import:AXIAL-0.4")
      (libsource (lib "eagle-import") (part "RESISTORPTH-1/4W"))
    )
    (comp (ref "R71")
      (value "390")
      (footprint "eagle-import:AXIAL-0.4")
      (libsource (lib "eagle-import") (part "RESISTORPTH-1/4W"))
    )
    (comp (ref "R72")
      (value "390")
      (footprint "eagle-import:AXIAL-0.4")
      (libsource (lib "eagle-import") (part "RESISTORPTH-1/4W"))
    )
    (comp (ref "R73")
      (value "390")
      (footprint "eagle-import:AXIAL-0.4")
      (libsource (lib "eagle-import") (part "RESISTORPTH-1/4W"))
    )
    (comp (ref "R74")
      (value "390")
      (footprint "eagle-import:AXIAL-0.4")
      (libsource (lib "eagle-import") (part "RESISTORPTH-1/4W"))
    )
    (comp (ref "R75")
      (value "390")
      (footprint "eagle-import:AXIAL-0.4")
      (libsource (lib "eagle-import") (part "RESISTORPTH-1/4W"))
    )
    (comp (ref "R76")
      (value "390")
      (footprint "eagle-import:AXIAL-0.4")
      (libsource (lib "eagle-import") (part "RESISTORPTH-1/4W"))
    )
    (comp (ref "R77")
      (value "390")
      (footprint "eagle-import:AXIAL-0.4")
      (libsource (lib "eagle-import") (part "RESISTORPTH-1/4W"))
    )
    (comp (ref "R78")
      (value "390")
      (footprint "eagle-import:AXIAL-0.4")
      (libsource (lib "eagle-import") (part "RESISTORPTH-1/4W"))
    )
    (comp (ref "R79")
      (value "390")
      (footprint "eagle-import:AXIAL-0.4")
      (libsource (lib "eagle-import") (part "RESISTORPTH-1/4W"))
    )
    (comp (ref "R80")
      (value "390")
      (footprint "eagle-import:AXIAL-0.4")
      (libsource (lib "eagle-import") (part "RESISTORPTH-1/4W"))
    )
    (comp (ref "R81")
      (value "390")
      (footprint "eagle-import:AXIAL-0.4")
      (libsource (lib "eagle-import") (part "RESISTORPTH-1/4W"))
    )
    (comp (ref "R82")
      (value "390")
      (footprint "eagle-import:AXIAL-0.4")
      (libsource (lib "eagle-import") (part "RESISTORPTH-1/4W"))
    )
    (comp (ref "R83")
      (value "390")
      (footprint "eagle-import:AXIAL-0.4")
      (libsource (lib "eagle-import") (part "RESISTORPTH-1/4W"))
    )
    (comp (ref "R84")
      (value "390")
      (footprint "eagle-import:AXIAL-0.4")
      (libsource (lib "eagle-import") (part "RESISTORPTH-1/4W"))
    )
    (comp (ref "R85")
      (value "390")
      (footprint "eagle-import:AXIAL-0.4")
      (libsource (lib "eagle-import") (part "RESISTORPTH-1/4W"))
    )
    (comp (ref "R86")
      (value "390")
      (footprint "eagle-import:AXIAL-0.4")
      (libsource (lib "eagle-import") (part "RESISTORPTH-1/4W"))
    )
    (comp (ref "R87")
      (value "390")
      (footprint "eagle-import:AXIAL-0.4")
      (libsource (lib "eagle-import") (part "RESISTORPTH-1/4W"))
    )
    (comp (ref "R88")
      (value "390")
      (footprint "eagle-import:AXIAL-0.4")
      (libsource (lib "eagle-import") (part "RESISTORPTH-1/4W"))
    )
    (comp (ref "R89")
      (value "390")
      (footprint "eagle-import:AXIAL-0.4")
      (libsource (lib "eagle-import") (part "RESISTORPTH-1/4W"))
    )
    (comp (ref "R90")
      (value "390")
      (footprint "eagle-import:AXIAL-0.4")
      (libsource (lib "eagle-import") (part "RESISTORPTH-1/4W"))
    )
    (comp (ref "R91")
      (value "390")
      (footprint "eagle-import:AXIAL-0.4")
      (libsource (lib "eagle-import") (part "RESISTORPTH-1/4W"))
    )
    (comp (ref "R92")
      (value "390")
      (footprint "eagle-import:AXIAL-0.4")
      (libsource (lib "eagle-import") (part "RESISTORPTH-1/4W"))
    )
    (comp (ref "R93")
      (value "390")
      (footprint "eagle-import:AXIAL-0.4")
      (libsource (lib "eagle-import") (part "RESISTORPTH-1/4W"))
    )
    (comp (ref "R94")
      (value "390")
      (footprint "eagle-import:AXIAL-0.4")
      (libsource (lib "eagle-import") (part "RESISTORPTH-1/4W"))
    )
    (comp (ref "R95")
      (value "390")
      (footprint "eagle-import:AXIAL-0.4")
      (libsource (lib "eagle-import") (part "RESISTORPTH-1/4W"))
    )
    (comp (ref "R96")
      (value "390")
      (footprint "eagle-import:AXIAL-0.4")
      (libsource (lib "eagle-import") (part "RESISTORPTH-1/4W"))
    )
    (comp (ref "U$1")
      (value "LEDMATRIX(HS2388)")
      (footprint "eagle-import:HS2388")
      (libsource (lib "eagle-import") (part "LEDMATRIX(HS2388)"))
    )
    (comp (ref "U$2")
      (value "LEDMATRIX(HS2388)")
      (footprint "eagle-import:HS2388")
      (libsource (lib "eagle-import") (part "LEDMATRIX(HS2388)"))
    )
    (comp (ref "U$3")
      (value "LEDMATRIX(HS2388)")
      (footprint "eagle-import:HS2388")
      (libsource (lib "eagle-import") (part "LEDMATRIX(HS2388)"))
    )
    (comp (ref "U$4")
      (value "LEDMATRIX(HS2388)")
      (footprint "eagle-import:HS2388")
      (libsource (lib "eagle-import") (part "LEDMATRIX(HS2388)"))
    )
  )
  (nets
    (net (code "1") (name "CLOCK") (class "Default")
      (node (ref "IC1") (pin "11") (pinfunction "SCK_11") (pintype "input"))
      (node (ref "IC2") (pin "11") (pinfunction "SCK_11") (pintype "input"))
      (node (ref "IC3") (pin "11") (pinfunction "SCK_11") (pintype "input"))
      (node (ref "IC4") (pin "11") (pinfunction "SCK_11") (pintype "input"))
      (node (ref "IC5") (pin "11") (pinfunction "SCK_11") (pintype "input"))
      (node (ref "IC6") (pin "11") (pinfunction "SCK_11") (pintype "input"))
      (node (ref "IC7") (pin "11") (pinfunction "SCK_11") (pintype "input"))
      (node (ref "IC8") (pin "11") (pinfunction "SCK_11") (pintype "input"))
      (node (ref "JP1") (pin "3") (pinfunction "3_3") (pintype "passive"))
    )
    (net (code "2") (name "GND") (class "Default")
      (node (ref "IC1") (pin "13") (pinfunction "G_13") (pintype "input"))
      (node (ref "IC1") (pin "8") (pinfunction "GND_8") (pintype "power_in"))
      (node (ref "IC2") (pin "13") (pinfunction "G_13") (pintype "input"))
      (node (ref "IC2") (pin "8") (pinfunction "GND_8") (pintype "power_in"))
      (node (ref "IC3") (pin "13") (pinfunction "G_13") (pintype "input"))
      (node (ref "IC3") (pin "8") (pinfunction "GND_8") (pintype "power_in"))
      (node (ref "IC4") (pin "13") (pinfunction "G_13") (pintype "input"))
      (node (ref "IC4") (pin "8") (pinfunction "GND_8") (pintype "power_in"))
      (node (ref "IC5") (pin "13") (pinfunction "G_13") (pintype "input"))
      (node (ref "IC5") (pin "8") (pinfunction "GND_8") (pintype "power_in"))
      (node (ref "IC6") (pin "13") (pinfunction "G_13") (pintype "input"))
      (node (ref "IC6") (pin "8") (pinfunction "GND_8") (pintype "power_in"))
      (node (ref "IC7") (pin "13") (pinfunction "G_13") (pintype "input"))
      (node (ref "IC7") (pin "8") (pinfunction "GND_8") (pintype "power_in"))
      (node (ref "IC8") (pin "13") (pinfunction "G_13") (pintype "input"))
      (node (ref "IC8") (pin "8") (pinfunction "GND_8") (pintype "power_in"))
      (node (ref "IC8") (pin "9") (pinfunction "QH*_9") (pintype "tri_state"))
      (node (ref "JP1") (pin "1") (pinfunction "1_1") (pintype "passive"))
      (node (ref "Q1") (pin "E") (pinfunction "E_E") (pintype "passive"))
      (node (ref "Q17") (pin "E") (pinfunction "E_E") (pintype "passive"))
      (node (ref "Q18") (pin "E") (pinfunction "E_E") (pintype "passive"))
      (node (ref "Q19") (pin "E") (pinfunction "E_E") (pintype "passive"))
      (node (ref "Q2") (pin "E") (pinfunction "E_E") (pintype "passive"))
      (node (ref "Q20") (pin "E") (pinfunction "E_E") (pintype "passive"))
      (node (ref "Q21") (pin "E") (pinfunction "E_E") (pintype "passive"))
      (node (ref "Q22") (pin "E") (pinfunction "E_E") (pintype "passive"))
      (node (ref "Q23") (pin "E") (pinfunction "E_E") (pintype "passive"))
      (node (ref "Q24") (pin "E") (pinfunction "E_E") (pintype "passive"))
      (node (ref "Q3") (pin "E") (pinfunction "E_E") (pintype "passive"))
      (node (ref "Q33") (pin "E") (pinfunction "E_E") (pintype "passive"))
      (node (ref "Q34") (pin "E") (pinfunction "E_E") (pintype "passive"))
      (node (ref "Q35") (pin "E") (pinfunction "E_E") (pintype "passive"))
      (node (ref "Q36") (pin "E") (pinfunction "E_E") (pintype "passive"))
      (node (ref "Q37") (pin "E") (pinfunction "E_E") (pintype "passive"))
      (node (ref "Q38") (pin "E") (pinfunction "E_E") (pintype "passive"))
      (node (ref "Q39") (pin "E") (pinfunction "E_E") (pintype "passive"))
      (node (ref "Q4") (pin "E") (pinfunction "E_E") (pintype "passive"))
      (node (ref "Q40") (pin "E") (pinfunction "E_E") (pintype "passive"))
      (node (ref "Q49") (pin "E") (pinfunction "E_E") (pintype "passive"))
      (node (ref "Q5") (pin "E") (pinfunction "E_E") (pintype "passive"))
      (node (ref "Q50") (pin "E") (pinfunction "E_E") (pintype "passive"))
      (node (ref "Q51") (pin "E") (pinfunction "E_E") (pintype "passive"))
      (node (ref "Q52") (pin "E") (pinfunction "E_E") (pintype "passive"))
      (node (ref "Q53") (pin "E") (pinfunction "E_E") (pintype "passive"))
      (node (ref "Q54") (pin "E") (pinfunction "E_E") (pintype "passive"))
      (node (ref "Q55") (pin "E") (pinfunction "E_E") (pintype "passive"))
      (node (ref "Q56") (pin "E") (pinfunction "E_E") (pintype "passive"))
      (node (ref "Q6") (pin "E") (pinfunction "E_E") (pintype "passive"))
      (node (ref "Q7") (pin "E") (pinfunction "E_E") (pintype "passive"))
      (node (ref "Q8") (pin "E") (pinfunction "E_E") (pintype "passive"))
    )
    (net (code "3") (name "LATCH") (class "Default")
      (node (ref "IC1") (pin "12") (pinfunction "RCK_12") (pintype "input"))
      (node (ref "IC2") (pin "12") (pinfunction "RCK_12") (pintype "input"))
      (node (ref "IC3") (pin "12") (pinfunction "RCK_12") (pintype "input"))
      (node (ref "IC4") (pin "12") (pinfunction "RCK_12") (pintype "input"))
      (node (ref "IC5") (pin "12") (pinfunction "RCK_12") (pintype "input"))
      (node (ref "IC6") (pin "12") (pinfunction "RCK_12") (pintype "input"))
      (node (ref "IC7") (pin "12") (pinfunction "RCK_12") (pintype "input"))
      (node (ref "IC8") (pin "12") (pinfunction "RCK_12") (pintype "input"))
      (node (ref "JP1") (pin "4") (pinfunction "4_4") (pintype "passive"))
    )
    (net (code "4") (name "Net-(IC1-QA)") (class "Default")
      (node (ref "IC1") (pin "15") (pinfunction "QA_15") (pintype "tri_state"))
      (node (ref "R1") (pin "P$1") (pinfunction "1_P$1") (pintype "passive"))
    )
    (net (code "5") (name "Net-(IC1-QB)") (class "Default")
      (node (ref "IC1") (pin "1") (pinfunction "QB_1") (pintype "tri_state"))
      (node (ref "R2") (pin "P$1") (pinfunction "1_P$1") (pintype "passive"))
    )
    (net (code "6") (name "Net-(IC1-QC)") (class "Default")
      (node (ref "IC1") (pin "2") (pinfunction "QC_2") (pintype "tri_state"))
      (node (ref "R3") (pin "P$1") (pinfunction "1_P$1") (pintype "passive"))
    )
    (net (code "7") (name "Net-(IC1-QD)") (class "Default")
      (node (ref "IC1") (pin "3") (pinfunction "QD_3") (pintype "tri_state"))
      (node (ref "R4") (pin "P$1") (pinfunction "1_P$1") (pintype "passive"))
    )
    (net (code "8") (name "Net-(IC1-QE)") (class "Default")
      (node (ref "IC1") (pin "4") (pinfunction "QE_4") (pintype "tri_state"))
      (node (ref "R5") (pin "P$1") (pinfunction "1_P$1") (pintype "passive"))
    )
    (net (code "9") (name "Net-(IC1-QF)") (class "Default")
      (node (ref "IC1") (pin "5") (pinfunction "QF_5") (pintype "tri_state"))
      (node (ref "R6") (pin "P$1") (pinfunction "1_P$1") (pintype "passive"))
    )
    (net (code "10") (name "Net-(IC1-QG)") (class "Default")
      (node (ref "IC1") (pin "6") (pinfunction "QG_6") (pintype "tri_state"))
      (node (ref "R7") (pin "P$1") (pinfunction "1_P$1") (pintype "passive"))
    )
    (net (code "11") (name "Net-(IC1-QH)") (class "Default")
      (node (ref "IC1") (pin "7") (pinfunction "QH_7") (pintype "tri_state"))
      (node (ref "R8") (pin "P$1") (pinfunction "1_P$1") (pintype "passive"))
    )
    (net (code "12") (name "Net-(IC1-QH*)") (class "Default")
      (node (ref "IC1") (pin "9") (pinfunction "QH*_9") (pintype "tri_state"))
      (node (ref "IC2") (pin "14") (pinfunction "SER_14") (pintype "input"))
    )
    (net (code "13") (name "Net-(IC2-QA)") (class "Default")
      (node (ref "IC2") (pin "15") (pinfunction "QA_15") (pintype "tri_state"))
      (node (ref "R9") (pin "P$1") (pinfunction "1_P$1") (pintype "passive"))
    )
    (net (code "14") (name "Net-(IC2-QB)") (class "Default")
      (node (ref "IC2") (pin "1") (pinfunction "QB_1") (pintype "tri_state"))
      (node (ref "R10") (pin "P$1") (pinfunction "1_P$1") (pintype "passive"))
    )
    (net (code "15") (name "Net-(IC2-QC)") (class "Default")
      (node (ref "IC2") (pin "2") (pinfunction "QC_2") (pintype "tri_state"))
      (node (ref "R11") (pin "P$1") (pinfunction "1_P$1") (pintype "passive"))
    )
    (net (code "16") (name "Net-(IC2-QD)") (class "Default")
      (node (ref "IC2") (pin "3") (pinfunction "QD_3") (pintype "tri_state"))
      (node (ref "R12") (pin "P$1") (pinfunction "1_P$1") (pintype "passive"))
    )
    (net (code "17") (name "Net-(IC2-QE)") (class "Default")
      (node (ref "IC2") (pin "4") (pinfunction "QE_4") (pintype "tri_state"))
      (node (ref "R13") (pin "P$1") (pinfunction "1_P$1") (pintype "passive"))
    )
    (net (code "18") (name "Net-(IC2-QF)") (class "Default")
      (node (ref "IC2") (pin "5") (pinfunction "QF_5") (pintype "tri_state"))
      (node (ref "R14") (pin "P$1") (pinfunction "1_P$1") (pintype "passive"))
    )
    (net (code "19") (name "Net-(IC2-QG)") (class "Default")
      (node (ref "IC2") (pin "6") (pinfunction "QG_6") (pintype "tri_state"))
      (node (ref "R15") (pin "P$1") (pinfunction "1_P$1") (pintype "passive"))
    )
    (net (code "20") (name "Net-(IC2-QH)") (class "Default")
      (node (ref "IC2") (pin "7") (pinfunction "QH_7") (pintype "tri_state"))
      (node (ref "R16") (pin "P$1") (pinfunction "1_P$1") (pintype "passive"))
    )
    (net (code "21") (name "Net-(IC2-QH*)") (class "Default")
      (node (ref "IC2") (pin "9") (pinfunction "QH*_9") (pintype "tri_state"))
      (node (ref "IC3") (pin "14") (pinfunction "SER_14") (pintype "input"))
    )
    (net (code "22") (name "Net-(IC3-QA)") (class "Default")
      (node (ref "IC3") (pin "15") (pinfunction "QA_15") (pintype "tri_state"))
      (node (ref "R25") (pin "P$1") (pinfunction "1_P$1") (pintype "passive"))
    )
    (net (code "23") (name "Net-(IC3-QB)") (class "Default")
      (node (ref "IC3") (pin "1") (pinfunction "QB_1") (pintype "tri_state"))
      (node (ref "R26") (pin "P$1") (pinfunction "1_P$1") (pintype "passive"))
    )
    (net (code "24") (name "Net-(IC3-QC)") (class "Default")
      (node (ref "IC3") (pin "2") (pinfunction "QC_2") (pintype "tri_state"))
      (node (ref "R27") (pin "P$1") (pinfunction "1_P$1") (pintype "passive"))
    )
    (net (code "25") (name "Net-(IC3-QD)") (class "Default")
      (node (ref "IC3") (pin "3") (pinfunction "QD_3") (pintype "tri_state"))
      (node (ref "R28") (pin "P$1") (pinfunction "1_P$1") (pintype "passive"))
    )
    (net (code "26") (name "Net-(IC3-QE)") (class "Default")
      (node (ref "IC3") (pin "4") (pinfunction "QE_4") (pintype "tri_state"))
      (node (ref "R29") (pin "P$1") (pinfunction "1_P$1") (pintype "passive"))
    )
    (net (code "27") (name "Net-(IC3-QF)") (class "Default")
      (node (ref "IC3") (pin "5") (pinfunction "QF_5") (pintype "tri_state"))
      (node (ref "R30") (pin "P$1") (pinfunction "1_P$1") (pintype "passive"))
    )
    (net (code "28") (name "Net-(IC3-QG)") (class "Default")
      (node (ref "IC3") (pin "6") (pinfunction "QG_6") (pintype "tri_state"))
      (node (ref "R31") (pin "P$1") (pinfunction "1_P$1") (pintype "passive"))
    )
    (net (code "29") (name "Net-(IC3-QH)") (class "Default")
      (node (ref "IC3") (pin "7") (pinfunction "QH_7") (pintype "tri_state"))
      (node (ref "R32") (pin "P$1") (pinfunction "1_P$1") (pintype "passive"))
    )
    (net (code "30") (name "Net-(IC3-QH*)") (class "Default")
      (node (ref "IC3") (pin "9") (pinfunction "QH*_9") (pintype "tri_state"))
      (node (ref "IC4") (pin "14") (pinfunction "SER_14") (pintype "input"))
    )
    (net (code "31") (name "Net-(IC4-QA)") (class "Default")
      (node (ref "IC4") (pin "15") (pinfunction "QA_15") (pintype "tri_state"))
      (node (ref "R33") (pin "P$1") (pinfunction "1_P$1") (pintype "passive"))
    )
    (net (code "32") (name "Net-(IC4-QB)") (class "Default")
      (node (ref "IC4") (pin "1") (pinfunction "QB_1") (pintype "tri_state"))
      (node (ref "R34") (pin "P$1") (pinfunction "1_P$1") (pintype "passive"))
    )
    (net (code "33") (name "Net-(IC4-QC)") (class "Default")
      (node (ref "IC4") (pin "2") (pinfunction "QC_2") (pintype "tri_state"))
      (node (ref "R35") (pin "P$1") (pinfunction "1_P$1") (pintype "passive"))
    )
    (net (code "34") (name "Net-(IC4-QD)") (class "Default")
      (node (ref "IC4") (pin "3") (pinfunction "QD_3") (pintype "tri_state"))
      (node (ref "R36") (pin "P$1") (pinfunction "1_P$1") (pintype "passive"))
    )
    (net (code "35") (name "Net-(IC4-QE)") (class "Default")
      (node (ref "IC4") (pin "4") (pinfunction "QE_4") (pintype "tri_state"))
      (node (ref "R37") (pin "P$1") (pinfunction "1_P$1") (pintype "passive"))
    )
    (net (code "36") (name "Net-(IC4-QF)") (class "Default")
      (node (ref "IC4") (pin "5") (pinfunction "QF_5") (pintype "tri_state"))
      (node (ref "R38") (pin "P$1") (pinfunction "1_P$1") (pintype "passive"))
    )
    (net (code "37") (name "Net-(IC4-QG)") (class "Default")
      (node (ref "IC4") (pin "6") (pinfunction "QG_6") (pintype "tri_state"))
      (node (ref "R39") (pin "P$1") (pinfunction "1_P$1") (pintype "passive"))
    )
    (net (code "38") (name "Net-(IC4-QH)") (class "Default")
      (node (ref "IC4") (pin "7") (pinfunction "QH_7") (pintype "tri_state"))
      (node (ref "R40") (pin "P$1") (pinfunction "1_P$1") (pintype "passive"))
    )
    (net (code "39") (name "Net-(IC4-QH*)") (class "Default")
      (node (ref "IC4") (pin "9") (pinfunction "QH*_9") (pintype "tri_state"))
      (node (ref "IC5") (pin "14") (pinfunction "SER_14") (pintype "input"))
    )
    (net (code "40") (name "Net-(IC5-QA)") (class "Default")
      (node (ref "IC5") (pin "15") (pinfunction "QA_15") (pintype "tri_state"))
      (node (ref "R49") (pin "P$1") (pinfunction "1_P$1") (pintype "passive"))
    )
    (net (code "41") (name "Net-(IC5-QB)") (class "Default")
      (node (ref "IC5") (pin "1") (pinfunction "QB_1") (pintype "tri_state"))
      (node (ref "R50") (pin "P$1") (pinfunction "1_P$1") (pintype "passive"))
    )
    (net (code "42") (name "Net-(IC5-QC)") (class "Default")
      (node (ref "IC5") (pin "2") (pinfunction "QC_2") (pintype "tri_state"))
      (node (ref "R51") (pin "P$1") (pinfunction "1_P$1") (pintype "passive"))
    )
    (net (code "43") (name "Net-(IC5-QD)") (class "Default")
      (node (ref "IC5") (pin "3") (pinfunction "QD_3") (pintype "tri_state"))
      (node (ref "R52") (pin "P$1") (pinfunction "1_P$1") (pintype "passive"))
    )
    (net (code "44") (name "Net-(IC5-QE)") (class "Default")
      (node (ref "IC5") (pin "4") (pinfunction "QE_4") (pintype "tri_state"))
      (node (ref "R53") (pin "P$1") (pinfunction "1_P$1") (pintype "passive"))
    )
    (net (code "45") (name "Net-(IC5-QF)") (class "Default")
      (node (ref "IC5") (pin "5") (pinfunction "QF_5") (pintype "tri_state"))
      (node (ref "R54") (pin "P$1") (pinfunction "1_P$1") (pintype "passive"))
    )
    (net (code "46") (name "Net-(IC5-QG)") (class "Default")
      (node (ref "IC5") (pin "6") (pinfunction "QG_6") (pintype "tri_state"))
      (node (ref "R55") (pin "P$1") (pinfunction "1_P$1") (pintype "passive"))
    )
    (net (code "47") (name "Net-(IC5-QH)") (class "Default")
      (node (ref "IC5") (pin "7") (pinfunction "QH_7") (pintype "tri_state"))
      (node (ref "R95") (pin "P$1") (pinfunction "1_P$1") (pintype "passive"))
    )
    (net (code "48") (name "Net-(IC5-QH*)") (class "Default")
      (node (ref "IC5") (pin "9") (pinfunction "QH*_9") (pintype "tri_state"))
      (node (ref "IC6") (pin "14") (pinfunction "SER_14") (pintype "input"))
    )
    (net (code "49") (name "Net-(IC6-QA)") (class "Default")
      (node (ref "IC6") (pin "15") (pinfunction "QA_15") (pintype "tri_state"))
      (node (ref "R56") (pin "P$1") (pinfunction "1_P$1") (pintype "passive"))
    )
    (net (code "50") (name "Net-(IC6-QB)") (class "Default")
      (node (ref "IC6") (pin "1") (pinfunction "QB_1") (pintype "tri_state"))
      (node (ref "R57") (pin "P$1") (pinfunction "1_P$1") (pintype "passive"))
    )
    (net (code "51") (name "Net-(IC6-QC)") (class "Default")
      (node (ref "IC6") (pin "2") (pinfunction "QC_2") (pintype "tri_state"))
      (node (ref "R58") (pin "P$1") (pinfunction "1_P$1") (pintype "passive"))
    )
    (net (code "52") (name "Net-(IC6-QD)") (class "Default")
      (node (ref "IC6") (pin "3") (pinfunction "QD_3") (pintype "tri_state"))
      (node (ref "R59") (pin "P$1") (pinfunction "1_P$1") (pintype "passive"))
    )
    (net (code "53") (name "Net-(IC6-QE)") (class "Default")
      (node (ref "IC6") (pin "4") (pinfunction "QE_4") (pintype "tri_state"))
      (node (ref "R60") (pin "P$1") (pinfunction "1_P$1") (pintype "passive"))
    )
    (net (code "54") (name "Net-(IC6-QF)") (class "Default")
      (node (ref "IC6") (pin "5") (pinfunction "QF_5") (pintype "tri_state"))
      (node (ref "R61") (pin "P$1") (pinfunction "1_P$1") (pintype "passive"))
    )
    (net (code "55") (name "Net-(IC6-QG)") (class "Default")
      (node (ref "IC6") (pin "6") (pinfunction "QG_6") (pintype "tri_state"))
      (node (ref "R62") (pin "P$1") (pinfunction "1_P$1") (pintype "passive"))
    )
    (net (code "56") (name "Net-(IC6-QH)") (class "Default")
      (node (ref "IC6") (pin "7") (pinfunction "QH_7") (pintype "tri_state"))
      (node (ref "R63") (pin "P$1") (pinfunction "1_P$1") (pintype "passive"))
    )
    (net (code "57") (name "Net-(IC6-QH*)") (class "Default")
      (node (ref "IC6") (pin "9") (pinfunction "QH*_9") (pintype "tri_state"))
      (node (ref "IC7") (pin "14") (pinfunction "SER_14") (pintype "input"))
    )
    (net (code "58") (name "Net-(IC7-QA)") (class "Default")
      (node (ref "IC7") (pin "15") (pinfunction "QA_15") (pintype "tri_state"))
      (node (ref "R96") (pin "P$1") (pinfunction "1_P$1") (pintype "passive"))
    )
    (net (code "59") (name "Net-(IC7-QB)") (class "Default")
      (node (ref "IC7") (pin "1") (pinfunction "QB_1") (pintype "tri_state"))
      (node (ref "R72") (pin "P$1") (pinfunction "1_P$1") (pintype "passive"))
    )
    (net (code "60") (name "Net-(IC7-QC)") (class "Default")
      (node (ref "IC7") (pin "2") (pinfunction "QC_2") (pintype "tri_state"))
      (node (ref "R73") (pin "P$1") (pinfunction "1_P$1") (pintype "passive"))
    )
    (net (code "61") (name "Net-(IC7-QD)") (class "Default")
      (node (ref "IC7") (pin "3") (pinfunction "QD_3") (pintype "tri_state"))
      (node (ref "R74") (pin "P$1") (pinfunction "1_P$1") (pintype "passive"))
    )
    (net (code "62") (name "Net-(IC7-QE)") (class "Default")
      (node (ref "IC7") (pin "4") (pinfunction "QE_4") (pintype "tri_state"))
      (node (ref "R75") (pin "P$1") (pinfunction "1_P$1") (pintype "passive"))
    )
    (net (code "63") (name "Net-(IC7-QF)") (class "Default")
      (node (ref "IC7") (pin "5") (pinfunction "QF_5") (pintype "tri_state"))
      (node (ref "R76") (pin "P$1") (pinfunction "1_P$1") (pintype "passive"))
    )
    (net (code "64") (name "Net-(IC7-QG)") (class "Default")
      (node (ref "IC7") (pin "6") (pinfunction "QG_6") (pintype "tri_state"))
      (node (ref "R77") (pin "P$1") (pinfunction "1_P$1") (pintype "passive"))
    )
    (net (code "65") (name "Net-(IC7-QH)") (class "Default")
      (node (ref "IC7") (pin "7") (pinfunction "QH_7") (pintype "tri_state"))
      (node (ref "R78") (pin "P$1") (pinfunction "1_P$1") (pintype "passive"))
    )
    (net (code "66") (name "Net-(IC7-QH*)") (class "Default")
      (node (ref "IC7") (pin "9") (pinfunction "QH*_9") (pintype "tri_state"))
      (node (ref "IC8") (pin "14") (pinfunction "SER_14") (pintype "input"))
    )
    (net (code "67") (name "Net-(IC8-QA)") (class "Default")
      (node (ref "IC8") (pin "15") (pinfunction "QA_15") (pintype "tri_state"))
      (node (ref "R79") (pin "P$1") (pinfunction "1_P$1") (pintype "passive"))
    )
    (net (code "68") (name "Net-(IC8-QB)") (class "Default")
      (node (ref "IC8") (pin "1") (pinfunction "QB_1") (pintype "tri_state"))
      (node (ref "R80") (pin "P$1") (pinfunction "1_P$1") (pintype "passive"))
    )
    (net (code "69") (name "Net-(IC8-QC)") (class "Default")
      (node (ref "IC8") (pin "2") (pinfunction "QC_2") (pintype "tri_state"))
      (node (ref "R81") (pin "P$1") (pinfunction "1_P$1") (pintype "passive"))
    )
    (net (code "70") (name "Net-(IC8-QD)") (class "Default")
      (node (ref "IC8") (pin "3") (pinfunction "QD_3") (pintype "tri_state"))
      (node (ref "R82") (pin "P$1") (pinfunction "1_P$1") (pintype "passive"))
    )
    (net (code "71") (name "Net-(IC8-QE)") (class "Default")
      (node (ref "IC8") (pin "4") (pinfunction "QE_4") (pintype "tri_state"))
      (node (ref "R83") (pin "P$1") (pinfunction "1_P$1") (pintype "passive"))
    )
    (net (code "72") (name "Net-(IC8-QF)") (class "Default")
      (node (ref "IC8") (pin "5") (pinfunction "QF_5") (pintype "tri_state"))
      (node (ref "R84") (pin "P$1") (pinfunction "1_P$1") (pintype "passive"))
    )
    (net (code "73") (name "Net-(IC8-QG)") (class "Default")
      (node (ref "IC8") (pin "6") (pinfunction "QG_6") (pintype "tri_state"))
      (node (ref "R85") (pin "P$1") (pinfunction "1_P$1") (pintype "passive"))
    )
    (net (code "74") (name "Net-(IC8-QH)") (class "Default")
      (node (ref "IC8") (pin "7") (pinfunction "QH_7") (pintype "tri_state"))
      (node (ref "R86") (pin "P$1") (pinfunction "1_P$1") (pintype "passive"))
    )
    (net (code "75") (name "Net-(R1-2)") (class "Default")
      (node (ref "Q1") (pin "B") (pinfunction "B_B") (pintype "passive"))
      (node (ref "R1") (pin "P$2") (pinfunction "2_P$2") (pintype "passive"))
    )
    (net (code "76") (name "Net-(R2-2)") (class "Default")
      (node (ref "Q2") (pin "B") (pinfunction "B_B") (pintype "passive"))
      (node (ref "R2") (pin "P$2") (pinfunction "2_P$2") (pintype "passive"))
    )
    (net (code "77") (name "Net-(R3-2)") (class "Default")
      (node (ref "Q3") (pin "B") (pinfunction "B_B") (pintype "passive"))
      (node (ref "R3") (pin "P$2") (pinfunction "2_P$2") (pintype "passive"))
    )
    (net (code "78") (name "Net-(R4-2)") (class "Default")
      (node (ref "Q4") (pin "B") (pinfunction "B_B") (pintype "passive"))
      (node (ref "R4") (pin "P$2") (pinfunction "2_P$2") (pintype "passive"))
    )
    (net (code "79") (name "Net-(R5-2)") (class "Default")
      (node (ref "Q5") (pin "B") (pinfunction "B_B") (pintype "passive"))
      (node (ref "R5") (pin "P$2") (pinfunction "2_P$2") (pintype "passive"))
    )
    (net (code "80") (name "Net-(R6-2)") (class "Default")
      (node (ref "Q6") (pin "B") (pinfunction "B_B") (pintype "passive"))
      (node (ref "R6") (pin "P$2") (pinfunction "2_P$2") (pintype "passive"))
    )
    (net (code "81") (name "Net-(R7-2)") (class "Default")
      (node (ref "Q7") (pin "B") (pinfunction "B_B") (pintype "passive"))
      (node (ref "R7") (pin "P$2") (pinfunction "2_P$2") (pintype "passive"))
    )
    (net (code "82") (name "Net-(R8-2)") (class "Default")
      (node (ref "Q8") (pin "B") (pinfunction "B_B") (pintype "passive"))
      (node (ref "R8") (pin "P$2") (pinfunction "2_P$2") (pintype "passive"))
    )
    (net (code "83") (name "Net-(R9-2)") (class "Default")
      (node (ref "Q9") (pin "B") (pinfunction "B_B") (pintype "passive"))
      (node (ref "R9") (pin "P$2") (pinfunction "2_P$2") (pintype "passive"))
    )
    (net (code "84") (name "Net-(R10-2)") (class "Default")
      (node (ref "Q10") (pin "B") (pinfunction "B_B") (pintype "passive"))
      (node (ref "R10") (pin "P$2") (pinfunction "2_P$2") (pintype "passive"))
    )
    (net (code "85") (name "Net-(R11-2)") (class "Default")
      (node (ref "Q11") (pin "B") (pinfunction "B_B") (pintype "passive"))
      (node (ref "R11") (pin "P$2") (pinfunction "2_P$2") (pintype "passive"))
    )
    (net (code "86") (name "Net-(R12-2)") (class "Default")
      (node (ref "Q12") (pin "B") (pinfunction "B_B") (pintype "passive"))
      (node (ref "R12") (pin "P$2") (pinfunction "2_P$2") (pintype "passive"))
    )
    (net (code "87") (name "Net-(R13-2)") (class "Default")
      (node (ref "Q13") (pin "B") (pinfunction "B_B") (pintype "passive"))
      (node (ref "R13") (pin "P$2") (pinfunction "2_P$2") (pintype "passive"))
    )
    (net (code "88") (name "Net-(R14-2)") (class "Default")
      (node (ref "Q14") (pin "B") (pinfunction "B_B") (pintype "passive"))
      (node (ref "R14") (pin "P$2") (pinfunction "2_P$2") (pintype "passive"))
    )
    (net (code "89") (name "Net-(R15-2)") (class "Default")
      (node (ref "Q15") (pin "B") (pinfunction "B_B") (pintype "passive"))
      (node (ref "R15") (pin "P$2") (pinfunction "2_P$2") (pintype "passive"))
    )
    (net (code "90") (name "Net-(R16-2)") (class "Default")
      (node (ref "Q16") (pin "B") (pinfunction "B_B") (pintype "passive"))
      (node (ref "R16") (pin "P$2") (pinfunction "2_P$2") (pintype "passive"))
    )
    (net (code "91") (name "Net-(R17-1)") (class "Default")
      (node (ref "Q9") (pin "E") (pinfunction "E_E") (pintype "passive"))
      (node (ref "R17") (pin "P$1") (pinfunction "1_P$1") (pintype "passive"))
    )
    (net (code "92") (name "Net-(R17-2)") (class "Default")
      (node (ref "R17") (pin "P$2") (pinfunction "2_P$2") (pintype "passive"))
      (node (ref "U$1") (pin "9") (pinfunction "L1_9") (pintype "bidirectional"))
    )
    (net (code "93") (name "Net-(R18-1)") (class "Default")
      (node (ref "Q10") (pin "E") (pinfunction "E_E") (pintype "passive"))
      (node (ref "R18") (pin "P$1") (pinfunction "1_P$1") (pintype "passive"))
    )
    (net (code "94") (name "Net-(R18-2)") (class "Default")
      (node (ref "R18") (pin "P$2") (pinfunction "2_P$2") (pintype "passive"))
      (node (ref "U$1") (pin "14") (pinfunction "L2_14") (pintype "bidirectional"))
    )
    (net (code "95") (name "Net-(R19-1)") (class "Default")
      (node (ref "Q11") (pin "E") (pinfunction "E_E") (pintype "passive"))
      (node (ref "R19") (pin "P$1") (pinfunction "1_P$1") (pintype "passive"))
    )
    (net (code "96") (name "Net-(R19-2)") (class "Default")
      (node (ref "R19") (pin "P$2") (pinfunction "2_P$2") (pintype "passive"))
      (node (ref "U$1") (pin "8") (pinfunction "L3_8") (pintype "bidirectional"))
    )
    (net (code "97") (name "Net-(R20-1)") (class "Default")
      (node (ref "Q12") (pin "E") (pinfunction "E_E") (pintype "passive"))
      (node (ref "R20") (pin "P$1") (pinfunction "1_P$1") (pintype "passive"))
    )
    (net (code "98") (name "Net-(R20-2)") (class "Default")
      (node (ref "R20") (pin "P$2") (pinfunction "2_P$2") (pintype "passive"))
      (node (ref "U$1") (pin "12") (pinfunction "L4_12") (pintype "bidirectional"))
    )
    (net (code "99") (name "Net-(R21-1)") (class "Default")
      (node (ref "Q13") (pin "E") (pinfunction "E_E") (pintype "passive"))
      (node (ref "R21") (pin "P$1") (pinfunction "1_P$1") (pintype "passive"))
    )
    (net (code "100") (name "Net-(R21-2)") (class "Default")
      (node (ref "R21") (pin "P$2") (pinfunction "2_P$2") (pintype "passive"))
      (node (ref "U$1") (pin "1") (pinfunction "L5_1") (pintype "bidirectional"))
    )
    (net (code "101") (name "Net-(R22-1)") (class "Default")
      (node (ref "Q14") (pin "E") (pinfunction "E_E") (pintype "passive"))
      (node (ref "R22") (pin "P$1") (pinfunction "1_P$1") (pintype "passive"))
    )
    (net (code "102") (name "Net-(R22-2)") (class "Default")
      (node (ref "R22") (pin "P$2") (pinfunction "2_P$2") (pintype "passive"))
      (node (ref "U$1") (pin "7") (pinfunction "L6_7") (pintype "bidirectional"))
    )
    (net (code "103") (name "Net-(R23-1)") (class "Default")
      (node (ref "Q15") (pin "E") (pinfunction "E_E") (pintype "passive"))
      (node (ref "R23") (pin "P$1") (pinfunction "1_P$1") (pintype "passive"))
    )
    (net (code "104") (name "Net-(R23-2)") (class "Default")
      (node (ref "R23") (pin "P$2") (pinfunction "2_P$2") (pintype "passive"))
      (node (ref "U$1") (pin "2") (pinfunction "L7_2") (pintype "bidirectional"))
    )
    (net (code "105") (name "Net-(R24-1)") (class "Default")
      (node (ref "Q16") (pin "E") (pinfunction "E_E") (pintype "passive"))
      (node (ref "R24") (pin "P$1") (pinfunction "1_P$1") (pintype "passive"))
    )
    (net (code "106") (name "Net-(R24-2)") (class "Default")
      (node (ref "R24") (pin "P$2") (pinfunction "2_P$2") (pintype "passive"))
      (node (ref "U$1") (pin "5") (pinfunction "L8_5") (pintype "bidirectional"))
    )
    (net (code "107") (name "Net-(R25-2)") (class "Default")
      (node (ref "Q17") (pin "B") (pinfunction "B_B") (pintype "passive"))
      (node (ref "R25") (pin "P$2") (pinfunction "2_P$2") (pintype "passive"))
    )
    (net (code "108") (name "Net-(R26-2)") (class "Default")
      (node (ref "Q18") (pin "B") (pinfunction "B_B") (pintype "passive"))
      (node (ref "R26") (pin "P$2") (pinfunction "2_P$2") (pintype "passive"))
    )
    (net (code "109") (name "Net-(R27-2)") (class "Default")
      (node (ref "Q19") (pin "B") (pinfunction "B_B") (pintype "passive"))
      (node (ref "R27") (pin "P$2") (pinfunction "2_P$2") (pintype "passive"))
    )
    (net (code "110") (name "Net-(R28-2)") (class "Default")
      (node (ref "Q20") (pin "B") (pinfunction "B_B") (pintype "passive"))
      (node (ref "R28") (pin "P$2") (pinfunction "2_P$2") (pintype "passive"))
    )
    (net (code "111") (name "Net-(R29-2)") (class "Default")
      (node (ref "Q21") (pin "B") (pinfunction "B_B") (pintype "passive"))
      (node (ref "R29") (pin "P$2") (pinfunction "2_P$2") (pintype "passive"))
    )
    (net (code "112") (name "Net-(R30-2)") (class "Default")
      (node (ref "Q22") (pin "B") (pinfunction "B_B") (pintype "passive"))
      (node (ref "R30") (pin "P$2") (pinfunction "2_P$2") (pintype "passive"))
    )
    (net (code "113") (name "Net-(R31-2)") (class "Default")
      (node (ref "Q23") (pin "B") (pinfunction "B_B") (pintype "passive"))
      (node (ref "R31") (pin "P$2") (pinfunction "2_P$2") (pintype "passive"))
    )
    (net (code "114") (name "Net-(R32-2)") (class "Default")
      (node (ref "Q24") (pin "B") (pinfunction "B_B") (pintype "passive"))
      (node (ref "R32") (pin "P$2") (pinfunction "2_P$2") (pintype "passive"))
    )
    (net (code "115") (name "Net-(R33-2)") (class "Default")
      (node (ref "Q25") (pin "B") (pinfunction "B_B") (pintype "passive"))
      (node (ref "R33") (pin "P$2") (pinfunction "2_P$2") (pintype "passive"))
    )
    (net (code "116") (name "Net-(R34-2)") (class "Default")
      (node (ref "Q26") (pin "B") (pinfunction "B_B") (pintype "passive"))
      (node (ref "R34") (pin "P$2") (pinfunction "2_P$2") (pintype "passive"))
    )
    (net (code "117") (name "Net-(R35-2)") (class "Default")
      (node (ref "Q27") (pin "B") (pinfunction "B_B") (pintype "passive"))
      (node (ref "R35") (pin "P$2") (pinfunction "2_P$2") (pintype "passive"))
    )
    (net (code "118") (name "Net-(R36-2)") (class "Default")
      (node (ref "Q28") (pin "B") (pinfunction "B_B") (pintype "passive"))
      (node (ref "R36") (pin "P$2") (pinfunction "2_P$2") (pintype "passive"))
    )
    (net (code "119") (name "Net-(R37-2)") (class "Default")
      (node (ref "Q29") (pin "B") (pinfunction "B_B") (pintype "passive"))
      (node (ref "R37") (pin "P$2") (pinfunction "2_P$2") (pintype "passive"))
    )
    (net (code "120") (name "Net-(R38-2)") (class "Default")
      (node (ref "Q30") (pin "B") (pinfunction "B_B") (pintype "passive"))
      (node (ref "R38") (pin "P$2") (pinfunction "2_P$2") (pintype "passive"))
    )
    (net (code "121") (name "Net-(R39-2)") (class "Default")
      (node (ref "Q31") (pin "B") (pinfunction "B_B") (pintype "passive"))
      (node (ref "R39") (pin "P$2") (pinfunction "2_P$2") (pintype "passive"))
    )
    (net (code "122") (name "Net-(R40-2)") (class "Default")
      (node (ref "Q32") (pin "B") (pinfunction "B_B") (pintype "passive"))
      (node (ref "R40") (pin "P$2") (pinfunction "2_P$2") (pintype "passive"))
    )
    (net (code "123") (name "Net-(R41-1)") (class "Default")
      (node (ref "Q25") (pin "E") (pinfunction "E_E") (pintype "passive"))
      (node (ref "R41") (pin "P$1") (pinfunction "1_P$1") (pintype "passive"))
    )
    (net (code "124") (name "Net-(R41-2)") (class "Default")
      (node (ref "R41") (pin "P$2") (pinfunction "2_P$2") (pintype "passive"))
      (node (ref "U$2") (pin "9") (pinfunction "L1_9") (pintype "bidirectional"))
    )
    (net (code "125") (name "Net-(R42-1)") (class "Default")
      (node (ref "Q26") (pin "E") (pinfunction "E_E") (pintype "passive"))
      (node (ref "R42") (pin "P$1") (pinfunction "1_P$1") (pintype "passive"))
    )
    (net (code "126") (name "Net-(R42-2)") (class "Default")
      (node (ref "R42") (pin "P$2") (pinfunction "2_P$2") (pintype "passive"))
      (node (ref "U$2") (pin "14") (pinfunction "L2_14") (pintype "bidirectional"))
    )
    (net (code "127") (name "Net-(R43-1)") (class "Default")
      (node (ref "Q27") (pin "E") (pinfunction "E_E") (pintype "passive"))
      (node (ref "R43") (pin "P$1") (pinfunction "1_P$1") (pintype "passive"))
    )
    (net (code "128") (name "Net-(R43-2)") (class "Default")
      (node (ref "R43") (pin "P$2") (pinfunction "2_P$2") (pintype "passive"))
      (node (ref "U$2") (pin "8") (pinfunction "L3_8") (pintype "bidirectional"))
    )
    (net (code "129") (name "Net-(R44-1)") (class "Default")
      (node (ref "Q28") (pin "E") (pinfunction "E_E") (pintype "passive"))
      (node (ref "R44") (pin "P$1") (pinfunction "1_P$1") (pintype "passive"))
    )
    (net (code "130") (name "Net-(R44-2)") (class "Default")
      (node (ref "R44") (pin "P$2") (pinfunction "2_P$2") (pintype "passive"))
      (node (ref "U$2") (pin "12") (pinfunction "L4_12") (pintype "bidirectional"))
    )
    (net (code "131") (name "Net-(R45-1)") (class "Default")
      (node (ref "Q29") (pin "E") (pinfunction "E_E") (pintype "passive"))
      (node (ref "R45") (pin "P$1") (pinfunction "1_P$1") (pintype "passive"))
    )
    (net (code "132") (name "Net-(R45-2)") (class "Default")
      (node (ref "R45") (pin "P$2") (pinfunction "2_P$2") (pintype "passive"))
      (node (ref "U$2") (pin "1") (pinfunction "L5_1") (pintype "bidirectional"))
    )
    (net (code "133") (name "Net-(R46-1)") (class "Default")
      (node (ref "Q30") (pin "E") (pinfunction "E_E") (pintype "passive"))
      (node (ref "R46") (pin "P$1") (pinfunction "1_P$1") (pintype "passive"))
    )
    (net (code "134") (name "Net-(R46-2)") (class "Default")
      (node (ref "R46") (pin "P$2") (pinfunction "2_P$2") (pintype "passive"))
      (node (ref "U$2") (pin "7") (pinfunction "L6_7") (pintype "bidirectional"))
    )
    (net (code "135") (name "Net-(R47-1)") (class "Default")
      (node (ref "Q31") (pin "E") (pinfunction "E_E") (pintype "passive"))
      (node (ref "R47") (pin "P$1") (pinfunction "1_P$1") (pintype "passive"))
    )
    (net (code "136") (name "Net-(R47-2)") (class "Default")
      (node (ref "R47") (pin "P$2") (pinfunction "2_P$2") (pintype "passive"))
      (node (ref "U$2") (pin "2") (pinfunction "L7_2") (pintype "bidirectional"))
    )
    (net (code "137") (name "Net-(R48-1)") (class "Default")
      (node (ref "Q32") (pin "E") (pinfunction "E_E") (pintype "passive"))
      (node (ref "R48") (pin "P$1") (pinfunction "1_P$1") (pintype "passive"))
    )
    (net (code "138") (name "Net-(R48-2)") (class "Default")
      (node (ref "R48") (pin "P$2") (pinfunction "2_P$2") (pintype "passive"))
      (node (ref "U$2") (pin "5") (pinfunction "L8_5") (pintype "bidirectional"))
    )
    (net (code "139") (name "Net-(R49-2)") (class "Default")
      (node (ref "Q33") (pin "B") (pinfunction "B_B") (pintype "passive"))
      (node (ref "R49") (pin "P$2") (pinfunction "2_P$2") (pintype "passive"))
    )
    (net (code "140") (name "Net-(R50-2)") (class "Default")
      (node (ref "Q34") (pin "B") (pinfunction "B_B") (pintype "passive"))
      (node (ref "R50") (pin "P$2") (pinfunction "2_P$2") (pintype "passive"))
    )
    (net (code "141") (name "Net-(R51-2)") (class "Default")
      (node (ref "Q35") (pin "B") (pinfunction "B_B") (pintype "passive"))
      (node (ref "R51") (pin "P$2") (pinfunction "2_P$2") (pintype "passive"))
    )
    (net (code "142") (name "Net-(R52-2)") (class "Default")
      (node (ref "Q36") (pin "B") (pinfunction "B_B") (pintype "passive"))
      (node (ref "R52") (pin "P$2") (pinfunction "2_P$2") (pintype "passive"))
    )
    (net (code "143") (name "Net-(R53-2)") (class "Default")
      (node (ref "Q37") (pin "B") (pinfunction "B_B") (pintype "passive"))
      (node (ref "R53") (pin "P$2") (pinfunction "2_P$2") (pintype "passive"))
    )
    (net (code "144") (name "Net-(R54-2)") (class "Default")
      (node (ref "Q38") (pin "B") (pinfunction "B_B") (pintype "passive"))
      (node (ref "R54") (pin "P$2") (pinfunction "2_P$2") (pintype "passive"))
    )
    (net (code "145") (name "Net-(R55-2)") (class "Default")
      (node (ref "Q39") (pin "B") (pinfunction "B_B") (pintype "passive"))
      (node (ref "R55") (pin "P$2") (pinfunction "2_P$2") (pintype "passive"))
    )
    (net (code "146") (name "Net-(R56-2)") (class "Default")
      (node (ref "Q41") (pin "B") (pinfunction "B_B") (pintype "passive"))
      (node (ref "R56") (pin "P$2") (pinfunction "2_P$2") (pintype "passive"))
    )
    (net (code "147") (name "Net-(R57-2)") (class "Default")
      (node (ref "Q42") (pin "B") (pinfunction "B_B") (pintype "passive"))
      (node (ref "R57") (pin "P$2") (pinfunction "2_P$2") (pintype "passive"))
    )
    (net (code "148") (name "Net-(R58-2)") (class "Default")
      (node (ref "Q43") (pin "B") (pinfunction "B_B") (pintype "passive"))
      (node (ref "R58") (pin "P$2") (pinfunction "2_P$2") (pintype "passive"))
    )
    (net (code "149") (name "Net-(R59-2)") (class "Default")
      (node (ref "Q44") (pin "B") (pinfunction "B_B") (pintype "passive"))
      (node (ref "R59") (pin "P$2") (pinfunction "2_P$2") (pintype "passive"))
    )
    (net (code "150") (name "Net-(R60-2)") (class "Default")
      (node (ref "Q45") (pin "B") (pinfunction "B_B") (pintype "passive"))
      (node (ref "R60") (pin "P$2") (pinfunction "2_P$2") (pintype "passive"))
    )
    (net (code "151") (name "Net-(R61-2)") (class "Default")
      (node (ref "Q46") (pin "B") (pinfunction "B_B") (pintype "passive"))
      (node (ref "R61") (pin "P$2") (pinfunction "2_P$2") (pintype "passive"))
    )
    (net (code "152") (name "Net-(R62-2)") (class "Default")
      (node (ref "Q47") (pin "B") (pinfunction "B_B") (pintype "passive"))
      (node (ref "R62") (pin "P$2") (pinfunction "2_P$2") (pintype "passive"))
    )
    (net (code "153") (name "Net-(R63-2)") (class "Default")
      (node (ref "Q48") (pin "B") (pinfunction "B_B") (pintype "passive"))
      (node (ref "R63") (pin "P$2") (pinfunction "2_P$2") (pintype "passive"))
    )
    (net (code "154") (name "Net-(R64-1)") (class "Default")
      (node (ref "Q41") (pin "E") (pinfunction "E_E") (pintype "passive"))
      (node (ref "R64") (pin "P$1") (pinfunction "1_P$1") (pintype "passive"))
    )
    (net (code "155") (name "Net-(R64-2)") (class "Default")
      (node (ref "R64") (pin "P$2") (pinfunction "2_P$2") (pintype "passive"))
      (node (ref "U$3") (pin "9") (pinfunction "L1_9") (pintype "bidirectional"))
    )
    (net (code "156") (name "Net-(R65-1)") (class "Default")
      (node (ref "Q42") (pin "E") (pinfunction "E_E") (pintype "passive"))
      (node (ref "R65") (pin "P$1") (pinfunction "1_P$1") (pintype "passive"))
    )
    (net (code "157") (name "Net-(R65-2)") (class "Default")
      (node (ref "R65") (pin "P$2") (pinfunction "2_P$2") (pintype "passive"))
      (node (ref "U$3") (pin "14") (pinfunction "L2_14") (pintype "bidirectional"))
    )
    (net (code "158") (name "Net-(R66-1)") (class "Default")
      (node (ref "Q43") (pin "E") (pinfunction "E_E") (pintype "passive"))
      (node (ref "R66") (pin "P$1") (pinfunction "1_P$1") (pintype "passive"))
    )
    (net (code "159") (name "Net-(R66-2)") (class "Default")
      (node (ref "R66") (pin "P$2") (pinfunction "2_P$2") (pintype "passive"))
      (node (ref "U$3") (pin "8") (pinfunction "L3_8") (pintype "bidirectional"))
    )
    (net (code "160") (name "Net-(R67-1)") (class "Default")
      (node (ref "Q44") (pin "E") (pinfunction "E_E") (pintype "passive"))
      (node (ref "R67") (pin "P$1") (pinfunction "1_P$1") (pintype "passive"))
    )
    (net (code "161") (name "Net-(R67-2)") (class "Default")
      (node (ref "R67") (pin "P$2") (pinfunction "2_P$2") (pintype "passive"))
      (node (ref "U$3") (pin "12") (pinfunction "L4_12") (pintype "bidirectional"))
    )
    (net (code "162") (name "Net-(R68-1)") (class "Default")
      (node (ref "Q45") (pin "E") (pinfunction "E_E") (pintype "passive"))
      (node (ref "R68") (pin "P$1") (pinfunction "1_P$1") (pintype "passive"))
    )
    (net (code "163") (name "Net-(R68-2)") (class "Default")
      (node (ref "R68") (pin "P$2") (pinfunction "2_P$2") (pintype "passive"))
      (node (ref "U$3") (pin "1") (pinfunction "L5_1") (pintype "bidirectional"))
    )
    (net (code "164") (name "Net-(R69-1)") (class "Default")
      (node (ref "Q46") (pin "E") (pinfunction "E_E") (pintype "passive"))
      (node (ref "R69") (pin "P$1") (pinfunction "1_P$1") (pintype "passive"))
    )
    (net (code "165") (name "Net-(R69-2)") (class "Default")
      (node (ref "R69") (pin "P$2") (pinfunction "2_P$2") (pintype "passive"))
      (node (ref "U$3") (pin "7") (pinfunction "L6_7") (pintype "bidirectional"))
    )
    (net (code "166") (name "Net-(R70-1)") (class "Default")
      (node (ref "Q47") (pin "E") (pinfunction "E_E") (pintype "passive"))
      (node (ref "R70") (pin "P$1") (pinfunction "1_P$1") (pintype "passive"))
    )
    (net (code "167") (name "Net-(R70-2)") (class "Default")
      (node (ref "R70") (pin "P$2") (pinfunction "2_P$2") (pintype "passive"))
      (node (ref "U$3") (pin "2") (pinfunction "L7_2") (pintype "bidirectional"))
    )
    (net (code "168") (name "Net-(R71-1)") (class "Default")
      (node (ref "Q48") (pin "E") (pinfunction "E_E") (pintype "passive"))
      (node (ref "R71") (pin "P$1") (pinfunction "1_P$1") (pintype "passive"))
    )
    (net (code "169") (name "Net-(R71-2)") (class "Default")
      (node (ref "R71") (pin "P$2") (pinfunction "2_P$2") (pintype "passive"))
      (node (ref "U$3") (pin "5") (pinfunction "L8_5") (pintype "bidirectional"))
    )
    (net (code "170") (name "Net-(R72-2)") (class "Default")
      (node (ref "Q50") (pin "B") (pinfunction "B_B") (pintype "passive"))
      (node (ref "R72") (pin "P$2") (pinfunction "2_P$2") (pintype "passive"))
    )
    (net (code "171") (name "Net-(R73-2)") (class "Default")
      (node (ref "Q51") (pin "B") (pinfunction "B_B") (pintype "passive"))
      (node (ref "R73") (pin "P$2") (pinfunction "2_P$2") (pintype "passive"))
    )
    (net (code "172") (name "Net-(R74-2)") (class "Default")
      (node (ref "Q52") (pin "B") (pinfunction "B_B") (pintype "passive"))
      (node (ref "R74") (pin "P$2") (pinfunction "2_P$2") (pintype "passive"))
    )
    (net (code "173") (name "Net-(R75-2)") (class "Default")
      (node (ref "Q53") (pin "B") (pinfunction "B_B") (pintype "passive"))
      (node (ref "R75") (pin "P$2") (pinfunction "2_P$2") (pintype "passive"))
    )
    (net (code "174") (name "Net-(R76-2)") (class "Default")
      (node (ref "Q54") (pin "B") (pinfunction "B_B") (pintype "passive"))
      (node (ref "R76") (pin "P$2") (pinfunction "2_P$2") (pintype "passive"))
    )
    (net (code "175") (name "Net-(R77-2)") (class "Default")
      (node (ref "Q55") (pin "B") (pinfunction "B_B") (pintype "passive"))
      (node (ref "R77") (pin "P$2") (pinfunction "2_P$2") (pintype "passive"))
    )
    (net (code "176") (name "Net-(R78-2)") (class "Default")
      (node (ref "Q56") (pin "B") (pinfunction "B_B") (pintype "passive"))
      (node (ref "R78") (pin "P$2") (pinfunction "2_P$2") (pintype "passive"))
    )
    (net (code "177") (name "Net-(R79-2)") (class "Default")
      (node (ref "Q57") (pin "B") (pinfunction "B_B") (pintype "passive"))
      (node (ref "R79") (pin "P$2") (pinfunction "2_P$2") (pintype "passive"))
    )
    (net (code "178") (name "Net-(R80-2)") (class "Default")
      (node (ref "Q58") (pin "B") (pinfunction "B_B") (pintype "passive"))
      (node (ref "R80") (pin "P$2") (pinfunction "2_P$2") (pintype "passive"))
    )
    (net (code "179") (name "Net-(R81-2)") (class "Default")
      (node (ref "Q59") (pin "B") (pinfunction "B_B") (pintype "passive"))
      (node (ref "R81") (pin "P$2") (pinfunction "2_P$2") (pintype "passive"))
    )
    (net (code "180") (name "Net-(R82-2)") (class "Default")
      (node (ref "Q60") (pin "B") (pinfunction "B_B") (pintype "passive"))
      (node (ref "R82") (pin "P$2") (pinfunction "2_P$2") (pintype "passive"))
    )
    (net (code "181") (name "Net-(R83-2)") (class "Default")
      (node (ref "Q61") (pin "B") (pinfunction "B_B") (pintype "passive"))
      (node (ref "R83") (pin "P$2") (pinfunction "2_P$2") (pintype "passive"))
    )
    (net (code "182") (name "Net-(R84-2)") (class "Default")
      (node (ref "Q62") (pin "B") (pinfunction "B_B") (pintype "passive"))
      (node (ref "R84") (pin "P$2") (pinfunction "2_P$2") (pintype "passive"))
    )
    (net (code "183") (name "Net-(R85-2)") (class "Default")
      (node (ref "Q63") (pin "B") (pinfunction "B_B") (pintype "passive"))
      (node (ref "R85") (pin "P$2") (pinfunction "2_P$2") (pintype "passive"))
    )
    (net (code "184") (name "Net-(R86-2)") (class "Default")
      (node (ref "Q64") (pin "B") (pinfunction "B_B") (pintype "passive"))
      (node (ref "R86") (pin "P$2") (pinfunction "2_P$2") (pintype "passive"))
    )
    (net (code "185") (name "Net-(R87-1)") (class "Default")
      (node (ref "Q57") (pin "E") (pinfunction "E_E") (pintype "passive"))
      (node (ref "R87") (pin "P$1") (pinfunction "1_P$1") (pintype "passive"))
    )
    (net (code "186") (name "Net-(R87-2)") (class "Default")
      (node (ref "R87") (pin "P$2") (pinfunction "2_P$2") (pintype "passive"))
      (node (ref "U$4") (pin "9") (pinfunction "L1_9") (pintype "bidirectional"))
    )
    (net (code "187") (name "Net-(R88-1)") (class "Default")
      (node (ref "Q58") (pin "E") (pinfunction "E_E") (pintype "passive"))
      (node (ref "R88") (pin "P$1") (pinfunction "1_P$1") (pintype "passive"))
    )
    (net (code "188") (name "Net-(R88-2)") (class "Default")
      (node (ref "R88") (pin "P$2") (pinfunction "2_P$2") (pintype "passive"))
      (node (ref "U$4") (pin "14") (pinfunction "L2_14") (pintype "bidirectional"))
    )
    (net (code "189") (name "Net-(R89-1)") (class "Default")
      (node (ref "Q59") (pin "E") (pinfunction "E_E") (pintype "passive"))
      (node (ref "R89") (pin "P$1") (pinfunction "1_P$1") (pintype "passive"))
    )
    (net (code "190") (name "Net-(R89-2)") (class "Default")
      (node (ref "R89") (pin "P$2") (pinfunction "2_P$2") (pintype "passive"))
      (node (ref "U$4") (pin "8") (pinfunction "L3_8") (pintype "bidirectional"))
    )
    (net (code "191") (name "Net-(R90-1)") (class "Default")
      (node (ref "Q60") (pin "E") (pinfunction "E_E") (pintype "passive"))
      (node (ref "R90") (pin "P$1") (pinfunction "1_P$1") (pintype "passive"))
    )
    (net (code "192") (name "Net-(R90-2)") (class "Default")
      (node (ref "R90") (pin "P$2") (pinfunction "2_P$2") (pintype "passive"))
      (node (ref "U$4") (pin "12") (pinfunction "L4_12") (pintype "bidirectional"))
    )
    (net (code "193") (name "Net-(R91-1)") (class "Default")
      (node (ref "Q61") (pin "E") (pinfunction "E_E") (pintype "passive"))
      (node (ref "R91") (pin "P$1") (pinfunction "1_P$1") (pintype "passive"))
    )
    (net (code "194") (name "Net-(R91-2)") (class "Default")
      (node (ref "R91") (pin "P$2") (pinfunction "2_P$2") (pintype "passive"))
      (node (ref "U$4") (pin "1") (pinfunction "L5_1") (pintype "bidirectional"))
    )
    (net (code "195") (name "Net-(R92-1)") (class "Default")
      (node (ref "Q62") (pin "E") (pinfunction "E_E") (pintype "passive"))
      (node (ref "R92") (pin "P$1") (pinfunction "1_P$1") (pintype "passive"))
    )
    (net (code "196") (name "Net-(R92-2)") (class "Default")
      (node (ref "R92") (pin "P$2") (pinfunction "2_P$2") (pintype "passive"))
      (node (ref "U$4") (pin "7") (pinfunction "L6_7") (pintype "bidirectional"))
    )
    (net (code "197") (name "Net-(R93-1)") (class "Default")
      (node (ref "Q63") (pin "E") (pinfunction "E_E") (pintype "passive"))
      (node (ref "R93") (pin "P$1") (pinfunction "1_P$1") (pintype "passive"))
    )
    (net (code "198") (name "Net-(R93-2)") (class "Default")
      (node (ref "R93") (pin "P$2") (pinfunction "2_P$2") (pintype "passive"))
      (node (ref "U$4") (pin "2") (pinfunction "L7_2") (pintype "bidirectional"))
    )
    (net (code "199") (name "Net-(R94-1)") (class "Default")
      (node (ref "Q64") (pin "E") (pinfunction "E_E") (pintype "passive"))
      (node (ref "R94") (pin "P$1") (pinfunction "1_P$1") (pintype "passive"))
    )
    (net (code "200") (name "Net-(R94-2)") (class "Default")
      (node (ref "R94") (pin "P$2") (pinfunction "2_P$2") (pintype "passive"))
      (node (ref "U$4") (pin "5") (pinfunction "L8_5") (pintype "bidirectional"))
    )
    (net (code "201") (name "Net-(R95-2)") (class "Default")
      (node (ref "Q40") (pin "B") (pinfunction "B_B") (pintype "passive"))
      (node (ref "R95") (pin "P$2") (pinfunction "2_P$2") (pintype "passive"))
    )
    (net (code "202") (name "Net-(R96-2)") (class "Default")
      (node (ref "Q49") (pin "B") (pinfunction "B_B") (pintype "passive"))
      (node (ref "R96") (pin "P$2") (pinfunction "2_P$2") (pintype "passive"))
    )
    (net (code "203") (name "Net-(U$1-C1)") (class "Default")
      (node (ref "Q1") (pin "C") (pinfunction "C_C") (pintype "passive"))
      (node (ref "U$1") (pin "13") (pinfunction "C1_13") (pintype "bidirectional"))
    )
    (net (code "204") (name "Net-(U$1-C2)") (class "Default")
      (node (ref "Q2") (pin "C") (pinfunction "C_C") (pintype "passive"))
      (node (ref "U$1") (pin "3") (pinfunction "C2_3") (pintype "bidirectional"))
    )
    (net (code "205") (name "Net-(U$1-C3)") (class "Default")
      (node (ref "Q3") (pin "C") (pinfunction "C_C") (pintype "passive"))
      (node (ref "U$1") (pin "4") (pinfunction "C3_4") (pintype "bidirectional"))
    )
    (net (code "206") (name "Net-(U$1-C4)") (class "Default")
      (node (ref "Q4") (pin "C") (pinfunction "C_C") (pintype "passive"))
      (node (ref "U$1") (pin "10") (pinfunction "C4_10") (pintype "bidirectional"))
    )
    (net (code "207") (name "Net-(U$1-C5)") (class "Default")
      (node (ref "Q5") (pin "C") (pinfunction "C_C") (pintype "passive"))
      (node (ref "U$1") (pin "6") (pinfunction "C5_6") (pintype "bidirectional"))
    )
    (net (code "208") (name "Net-(U$1-C6)") (class "Default")
      (node (ref "Q6") (pin "C") (pinfunction "C_C") (pintype "passive"))
      (node (ref "U$1") (pin "11") (pinfunction "C6_11") (pintype "bidirectional"))
    )
    (net (code "209") (name "Net-(U$1-C7)") (class "Default")
      (node (ref "Q7") (pin "C") (pinfunction "C_C") (pintype "passive"))
      (node (ref "U$1") (pin "15") (pinfunction "C7_15") (pintype "bidirectional"))
    )
    (net (code "210") (name "Net-(U$1-C8)") (class "Default")
      (node (ref "Q8") (pin "C") (pinfunction "C_C") (pintype "passive"))
      (node (ref "U$1") (pin "16") (pinfunction "C8_16") (pintype "bidirectional"))
    )
    (net (code "211") (name "Net-(U$2-C1)") (class "Default")
      (node (ref "Q17") (pin "C") (pinfunction "C_C") (pintype "passive"))
      (node (ref "U$2") (pin "13") (pinfunction "C1_13") (pintype "bidirectional"))
    )
    (net (code "212") (name "Net-(U$2-C2)") (class "Default")
      (node (ref "Q18") (pin "C") (pinfunction "C_C") (pintype "passive"))
      (node (ref "U$2") (pin "3") (pinfunction "C2_3") (pintype "bidirectional"))
    )
    (net (code "213") (name "Net-(U$2-C3)") (class "Default")
      (node (ref "Q19") (pin "C") (pinfunction "C_C") (pintype "passive"))
      (node (ref "U$2") (pin "4") (pinfunction "C3_4") (pintype "bidirectional"))
    )
    (net (code "214") (name "Net-(U$2-C4)") (class "Default")
      (node (ref "Q20") (pin "C") (pinfunction "C_C") (pintype "passive"))
      (node (ref "U$2") (pin "10") (pinfunction "C4_10") (pintype "bidirectional"))
    )
    (net (code "215") (name "Net-(U$2-C5)") (class "Default")
      (node (ref "Q21") (pin "C") (pinfunction "C_C") (pintype "passive"))
      (node (ref "U$2") (pin "6") (pinfunction "C5_6") (pintype "bidirectional"))
    )
    (net (code "216") (name "Net-(U$2-C6)") (class "Default")
      (node (ref "Q22") (pin "C") (pinfunction "C_C") (pintype "passive"))
      (node (ref "U$2") (pin "11") (pinfunction "C6_11") (pintype "bidirectional"))
    )
    (net (code "217") (name "Net-(U$2-C7)") (class "Default")
      (node (ref "Q23") (pin "C") (pinfunction "C_C") (pintype "passive"))
      (node (ref "U$2") (pin "15") (pinfunction "C7_15") (pintype "bidirectional"))
    )
    (net (code "218") (name "Net-(U$2-C8)") (class "Default")
      (node (ref "Q24") (pin "C") (pinfunction "C_C") (pintype "passive"))
      (node (ref "U$2") (pin "16") (pinfunction "C8_16") (pintype "bidirectional"))
    )
    (net (code "219") (name "Net-(U$3-C1)") (class "Default")
      (node (ref "Q33") (pin "C") (pinfunction "C_C") (pintype "passive"))
      (node (ref "U$3") (pin "13") (pinfunction "C1_13") (pintype "bidirectional"))
    )
    (net (code "220") (name "Net-(U$3-C2)") (class "Default")
      (node (ref "Q34") (pin "C") (pinfunction "C_C") (pintype "passive"))
      (node (ref "U$3") (pin "3") (pinfunction "C2_3") (pintype "bidirectional"))
    )
    (net (code "221") (name "Net-(U$3-C3)") (class "Default")
      (node (ref "Q35") (pin "C") (pinfunction "C_C") (pintype "passive"))
      (node (ref "U$3") (pin "4") (pinfunction "C3_4") (pintype "bidirectional"))
    )
    (net (code "222") (name "Net-(U$3-C4)") (class "Default")
      (node (ref "Q36") (pin "C") (pinfunction "C_C") (pintype "passive"))
      (node (ref "U$3") (pin "10") (pinfunction "C4_10") (pintype "bidirectional"))
    )
    (net (code "223") (name "Net-(U$3-C5)") (class "Default")
      (node (ref "Q37") (pin "C") (pinfunction "C_C") (pintype "passive"))
      (node (ref "U$3") (pin "6") (pinfunction "C5_6") (pintype "bidirectional"))
    )
    (net (code "224") (name "Net-(U$3-C6)") (class "Default")
      (node (ref "Q38") (pin "C") (pinfunction "C_C") (pintype "passive"))
      (node (ref "U$3") (pin "11") (pinfunction "C6_11") (pintype "bidirectional"))
    )
    (net (code "225") (name "Net-(U$3-C7)") (class "Default")
      (node (ref "Q39") (pin "C") (pinfunction "C_C") (pintype "passive"))
      (node (ref "U$3") (pin "15") (pinfunction "C7_15") (pintype "bidirectional"))
    )
    (net (code "226") (name "Net-(U$3-C8)") (class "Default")
      (node (ref "Q40") (pin "C") (pinfunction "C_C") (pintype "passive"))
      (node (ref "U$3") (pin "16") (pinfunction "C8_16") (pintype "bidirectional"))
    )
    (net (code "227") (name "Net-(U$4-C1)") (class "Default")
      (node (ref "Q49") (pin "C") (pinfunction "C_C") (pintype "passive"))
      (node (ref "U$4") (pin "13") (pinfunction "C1_13") (pintype "bidirectional"))
    )
    (net (code "228") (name "Net-(U$4-C2)") (class "Default")
      (node (ref "Q50") (pin "C") (pinfunction "C_C") (pintype "passive"))
      (node (ref "U$4") (pin "3") (pinfunction "C2_3") (pintype "bidirectional"))
    )
    (net (code "229") (name "Net-(U$4-C3)") (class "Default")
      (node (ref "Q51") (pin "C") (pinfunction "C_C") (pintype "passive"))
      (node (ref "U$4") (pin "4") (pinfunction "C3_4") (pintype "bidirectional"))
    )
    (net (code "230") (name "Net-(U$4-C4)") (class "Default")
      (node (ref "Q52") (pin "C") (pinfunction "C_C") (pintype "passive"))
      (node (ref "U$4") (pin "10") (pinfunction "C4_10") (pintype "bidirectional"))
    )
    (net (code "231") (name "Net-(U$4-C5)") (class "Default")
      (node (ref "Q53") (pin "C") (pinfunction "C_C") (pintype "passive"))
      (node (ref "U$4") (pin "6") (pinfunction "C5_6") (pintype "bidirectional"))
    )
    (net (code "232") (name "Net-(U$4-C6)") (class "Default")
      (node (ref "Q54") (pin "C") (pinfunction "C_C") (pintype "passive"))
      (node (ref "U$4") (pin "11") (pinfunction "C6_11") (pintype "bidirectional"))
    )
    (net (code "233") (name "Net-(U$4-C7)") (class "Default")
      (node (ref "Q55") (pin "C") (pinfunction "C_C") (pintype "passive"))
      (node (ref "U$4") (pin "15") (pinfunction "C7_15") (pintype "bidirectional"))
    )
    (net (code "234") (name "Net-(U$4-C8)") (class "Default")
      (node (ref "Q56") (pin "C") (pinfunction "C_C") (pintype "passive"))
      (node (ref "U$4") (pin "16") (pinfunction "C8_16") (pintype "bidirectional"))
    )
    (net (code "235") (name "SERIALIN") (class "Default")
      (node (ref "IC1") (pin "14") (pinfunction "SER_14") (pintype "input"))
      (node (ref "JP1") (pin "2") (pinfunction "2_2") (pintype "passive"))
    )
    (net (code "236") (name "VCC") (class "Default")
      (node (ref "IC1") (pin "10") (pinfunction "SCL_10") (pintype "input"))
      (node (ref "IC1") (pin "16") (pinfunction "VCC_16") (pintype "power_in"))
      (node (ref "IC2") (pin "10") (pinfunction "SCL_10") (pintype "input"))
      (node (ref "IC2") (pin "16") (pinfunction "VCC_16") (pintype "power_in"))
      (node (ref "IC3") (pin "10") (pinfunction "SCL_10") (pintype "input"))
      (node (ref "IC3") (pin "16") (pinfunction "VCC_16") (pintype "power_in"))
      (node (ref "IC4") (pin "10") (pinfunction "SCL_10") (pintype "input"))
      (node (ref "IC4") (pin "16") (pinfunction "VCC_16") (pintype "power_in"))
      (node (ref "IC5") (pin "10") (pinfunction "SCL_10") (pintype "input"))
      (node (ref "IC5") (pin "16") (pinfunction "VCC_16") (pintype "power_in"))
      (node (ref "IC6") (pin "10") (pinfunction "SCL_10") (pintype "input"))
      (node (ref "IC6") (pin "16") (pinfunction "VCC_16") (pintype "power_in"))
      (node (ref "IC7") (pin "10") (pinfunction "SCL_10") (pintype "input"))
      (node (ref "IC7") (pin "16") (pinfunction "VCC_16") (pintype "power_in"))
      (node (ref "IC8") (pin "10") (pinfunction "SCL_10") (pintype "input"))
      (node (ref "IC8") (pin "16") (pinfunction "VCC_16") (pintype "power_in"))
      (node (ref "JP1") (pin "5") (pinfunction "5_5") (pintype "passive"))
      (node (ref "Q10") (pin "C") (pinfunction "C_C") (pintype "passive"))
      (node (ref "Q11") (pin "C") (pinfunction "C_C") (pintype "passive"))
      (node (ref "Q12") (pin "C") (pinfunction "C_C") (pintype "passive"))
      (node (ref "Q13") (pin "C") (pinfunction "C_C") (pintype "passive"))
      (node (ref "Q14") (pin "C") (pinfunction "C_C") (pintype "passive"))
      (node (ref "Q15") (pin "C") (pinfunction "C_C") (pintype "passive"))
      (node (ref "Q16") (pin "C") (pinfunction "C_C") (pintype "passive"))
      (node (ref "Q25") (pin "C") (pinfunction "C_C") (pintype "passive"))
      (node (ref "Q26") (pin "C") (pinfunction "C_C") (pintype "passive"))
      (node (ref "Q27") (pin "C") (pinfunction "C_C") (pintype "passive"))
      (node (ref "Q28") (pin "C") (pinfunction "C_C") (pintype "passive"))
      (node (ref "Q29") (pin "C") (pinfunction "C_C") (pintype "passive"))
      (node (ref "Q30") (pin "C") (pinfunction "C_C") (pintype "passive"))
      (node (ref "Q31") (pin "C") (pinfunction "C_C") (pintype "passive"))
      (node (ref "Q32") (pin "C") (pinfunction "C_C") (pintype "passive"))
      (node (ref "Q41") (pin "C") (pinfunction "C_C") (pintype "passive"))
      (node (ref "Q42") (pin "C") (pinfunction "C_C") (pintype "passive"))
      (node (ref "Q43") (pin "C") (pinfunction "C_C") (pintype "passive"))
      (node (ref "Q44") (pin "C") (pinfunction "C_C") (pintype "passive"))
      (node (ref "Q45") (pin "C") (pinfunction "C_C") (pintype "passive"))
      (node (ref "Q46") (pin "C") (pinfunction "C_C") (pintype "passive"))
      (node (ref "Q47") (pin "C") (pinfunction "C_C") (pintype "passive"))
      (node (ref "Q48") (pin "C") (pinfunction "C_C") (pintype "passive"))
      (node (ref "Q57") (pin "C") (pinfunction "C_C") (pintype "passive"))
      (node (ref "Q58") (pin "C") (pinfunction "C_C") (pintype "passive"))
      (node (ref "Q59") (pin "C") (pinfunction "C_C") (pintype "passive"))
      (node (ref "Q60") (pin "C") (pinfunction "C_C") (pintype "passive"))
      (node (ref "Q61") (pin "C") (pinfunction "C_C") (pintype "passive"))
      (node (ref "Q62") (pin "C") (pinfunction "C_C") (pintype "passive"))
      (node (ref "Q63") (pin "C") (pinfunction "C_C") (pintype "passive"))
      (node (ref "Q64") (pin "C") (pinfunction "C_C") (pintype "passive"))
      (node (ref "Q9") (pin "C") (pinfunction "C_C") (pintype "passive"))
    )
  )
)
